# Tractive_System_Board_Rev3.net
KiCad netlist of a schematic drawn in EAGLE
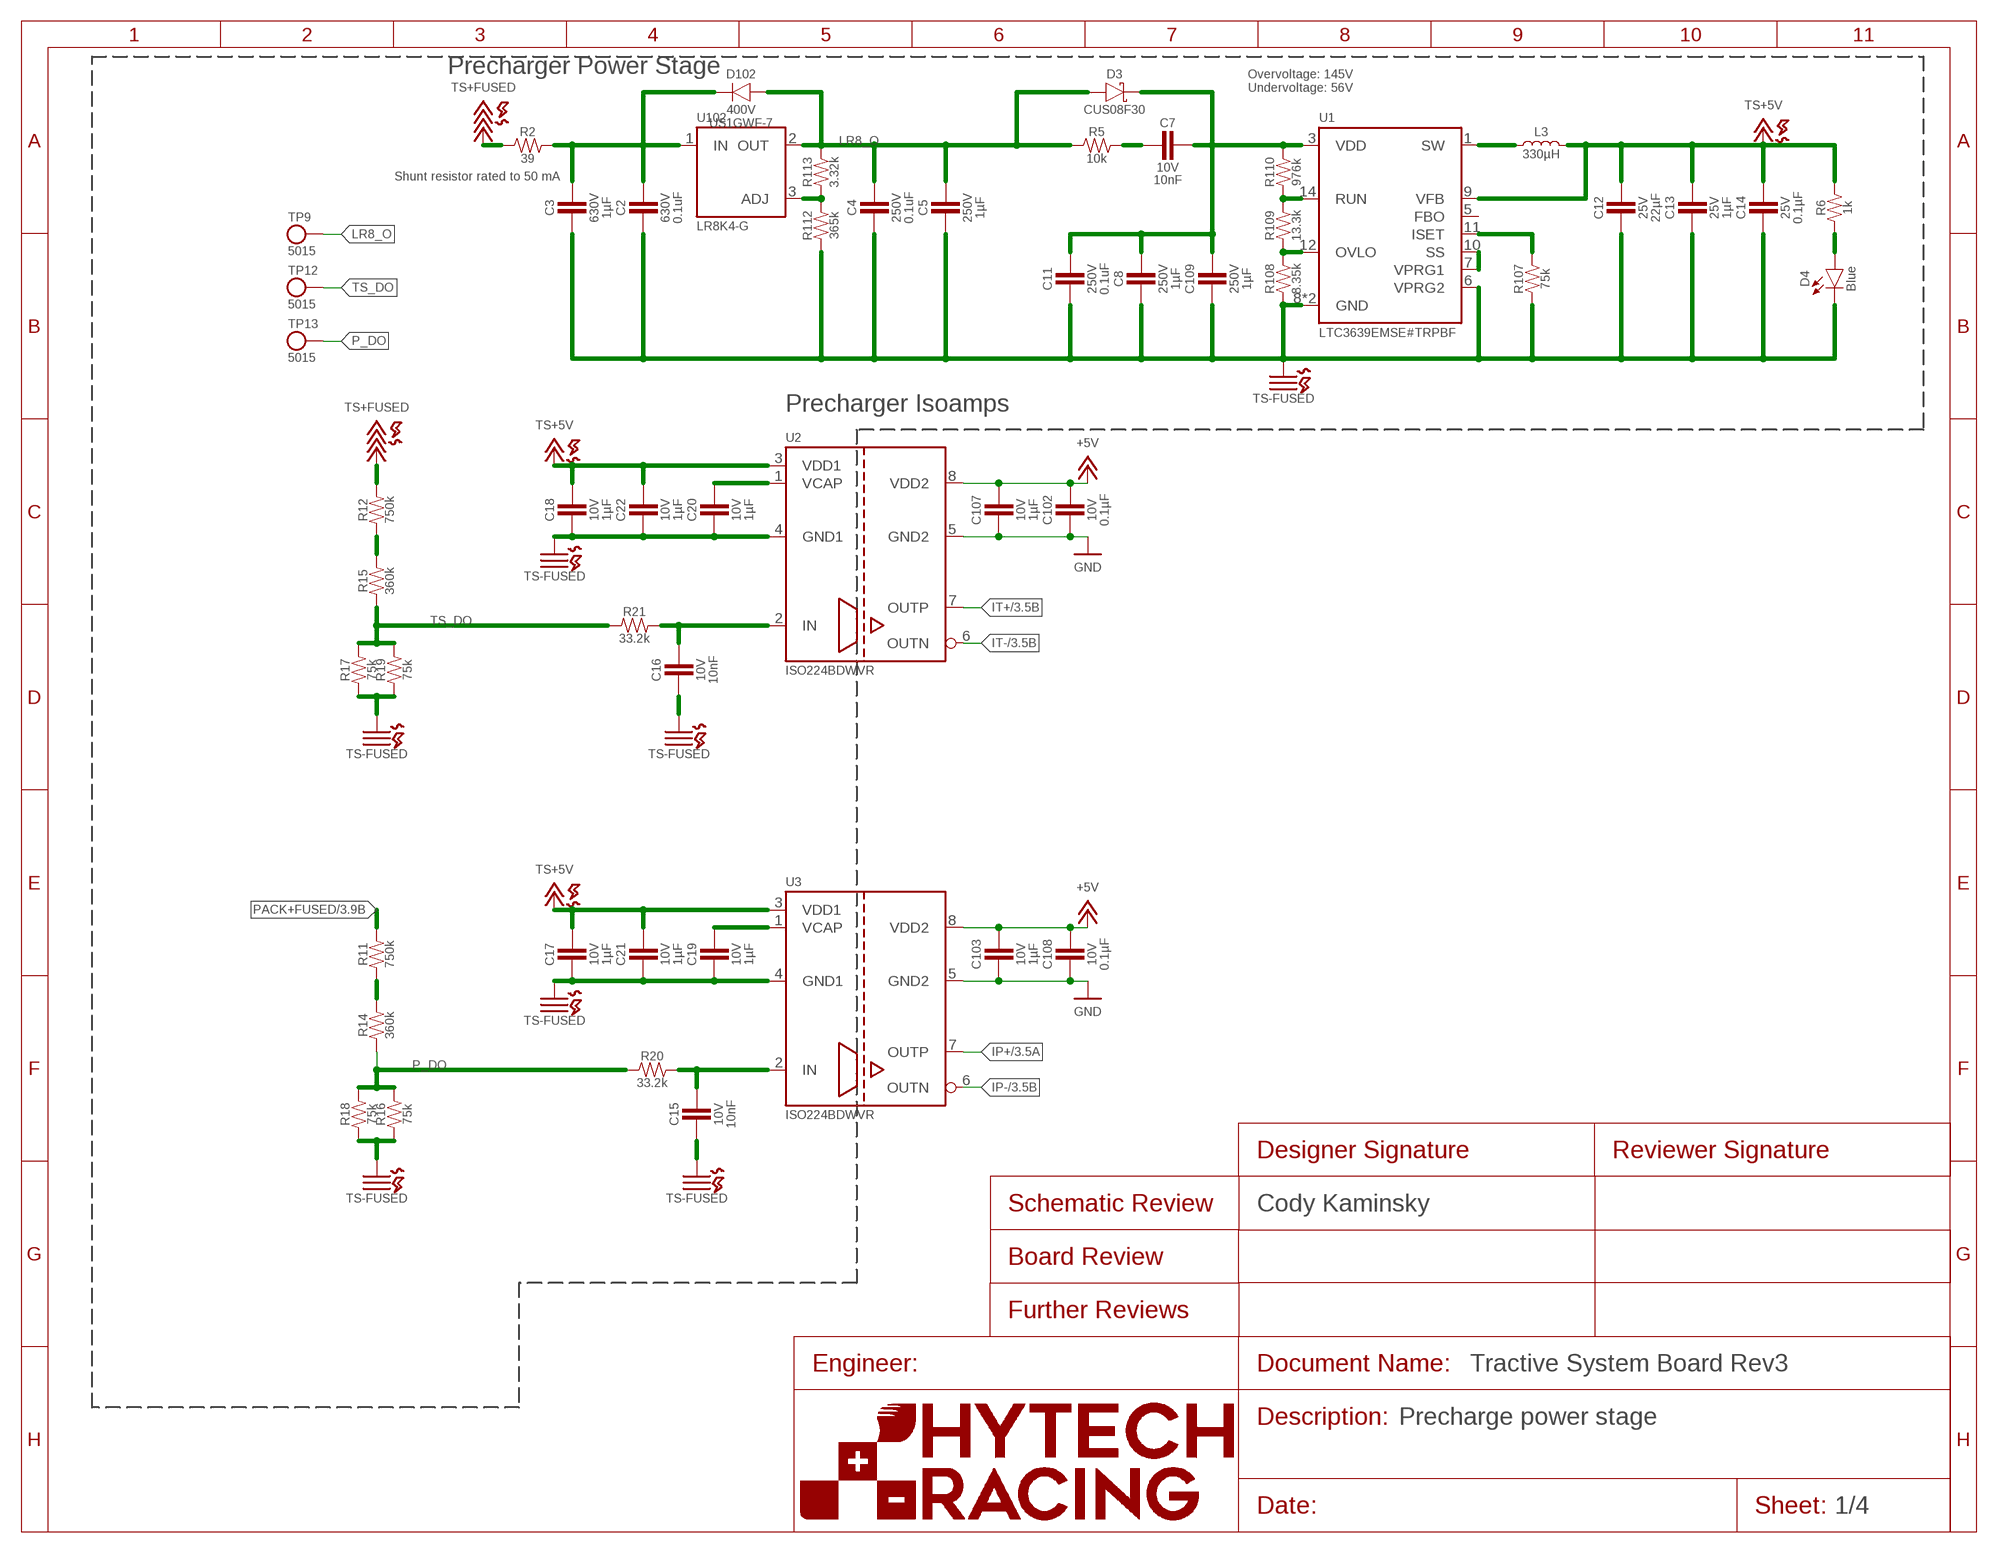
[diagram p0: schematic, sheet 1]
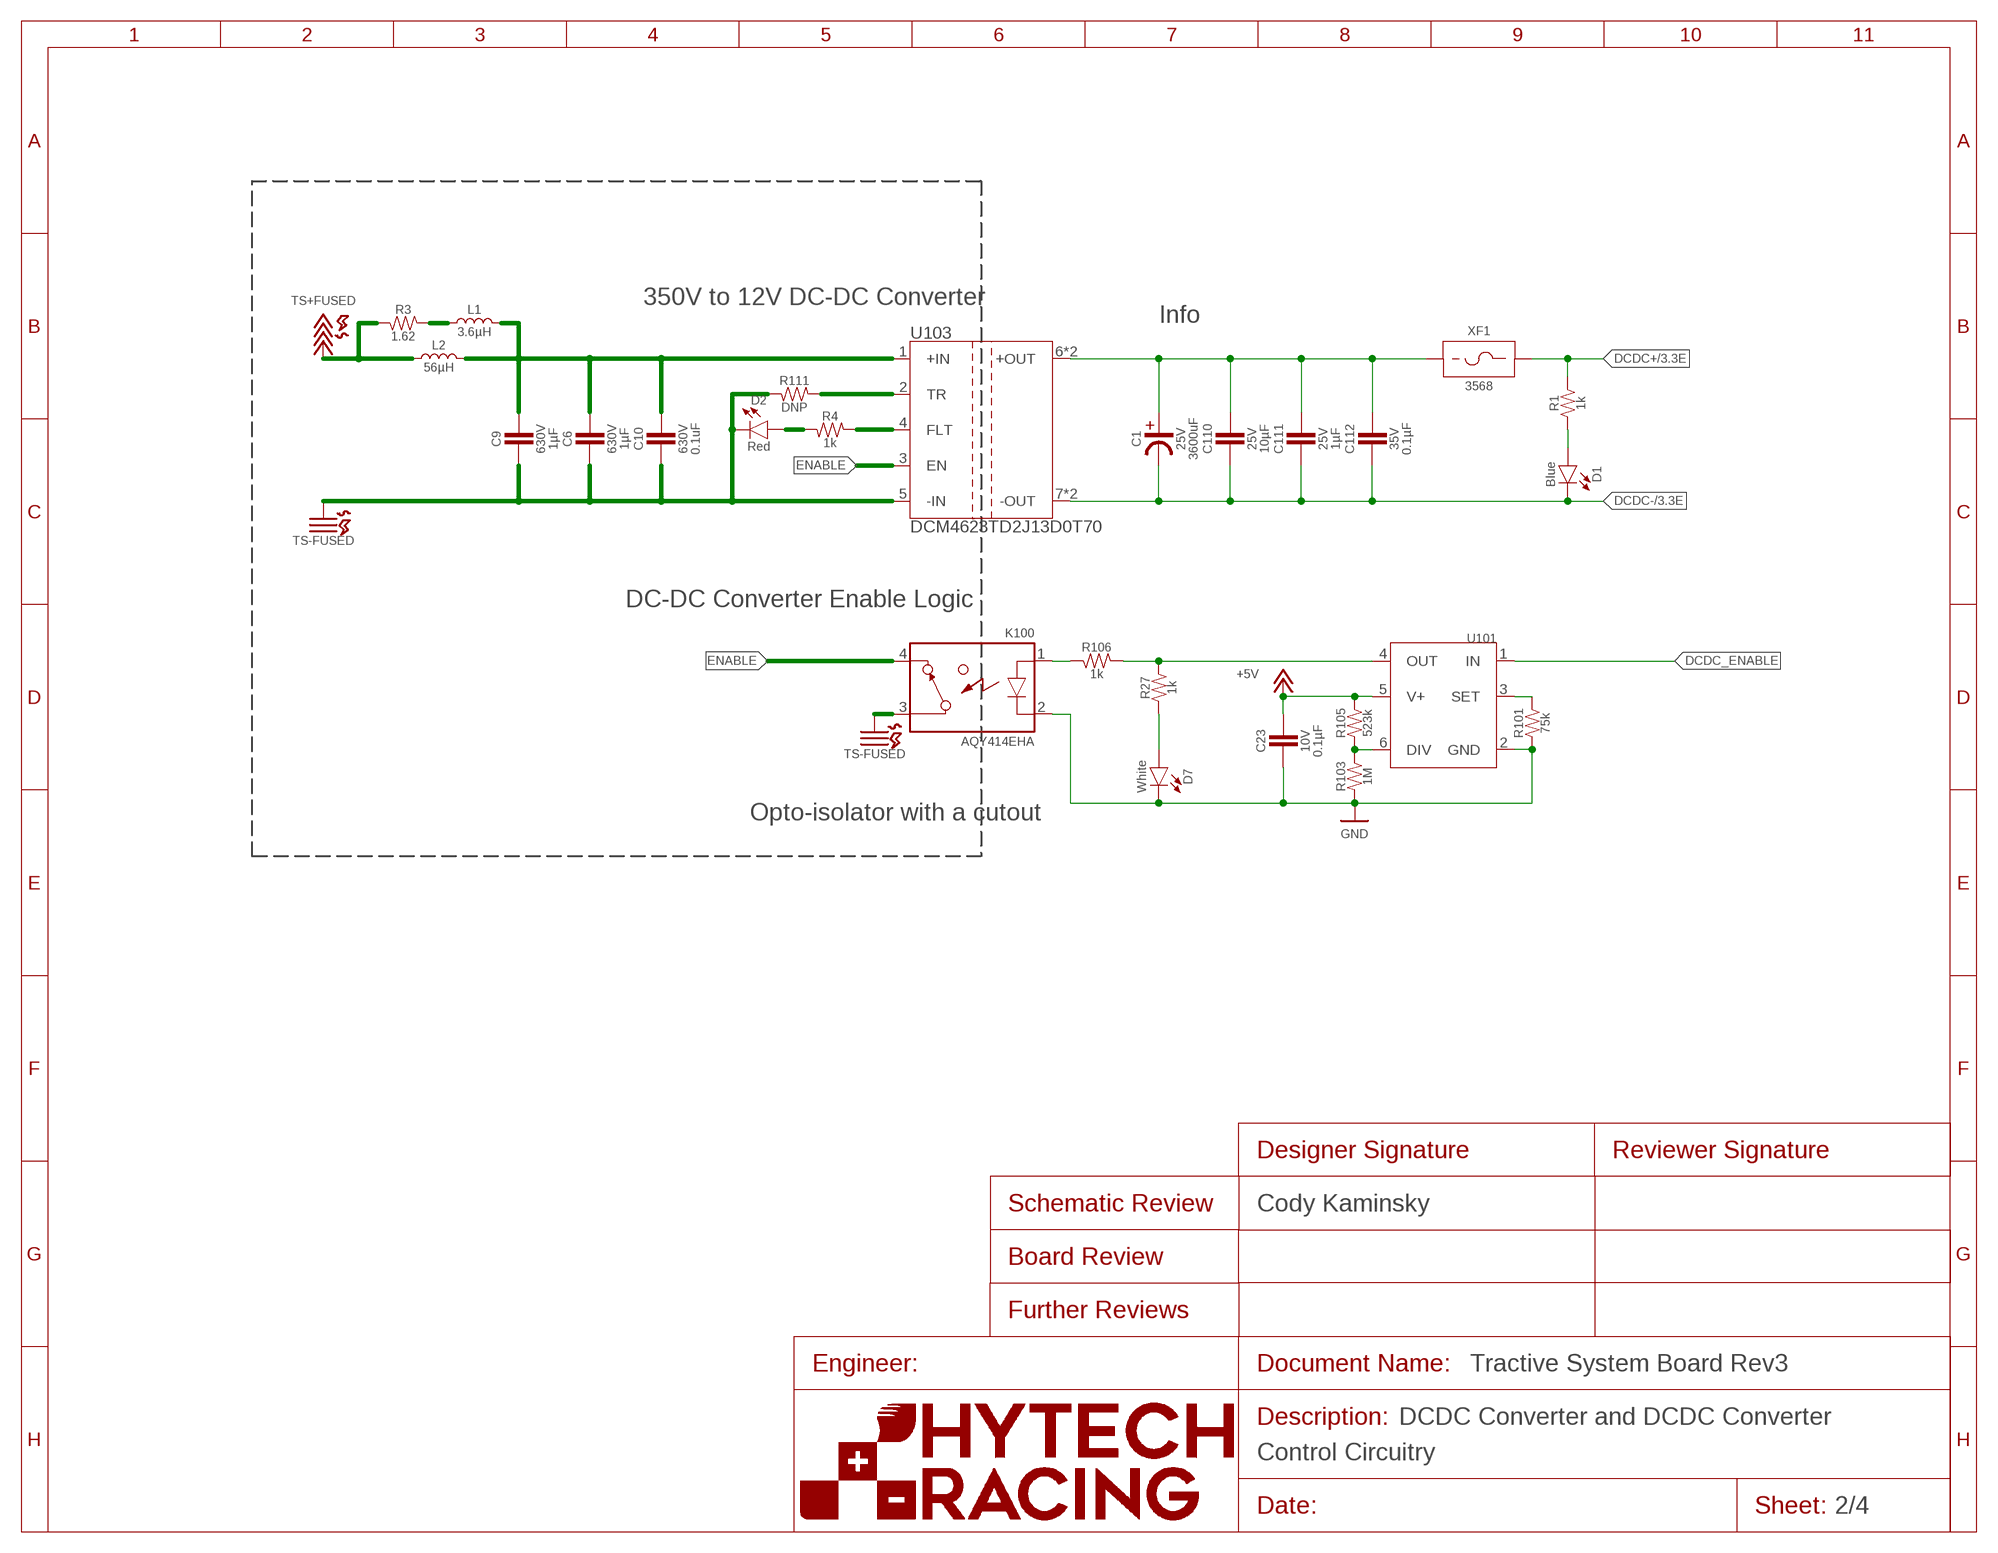
[diagram p1: schematic, sheet 2]
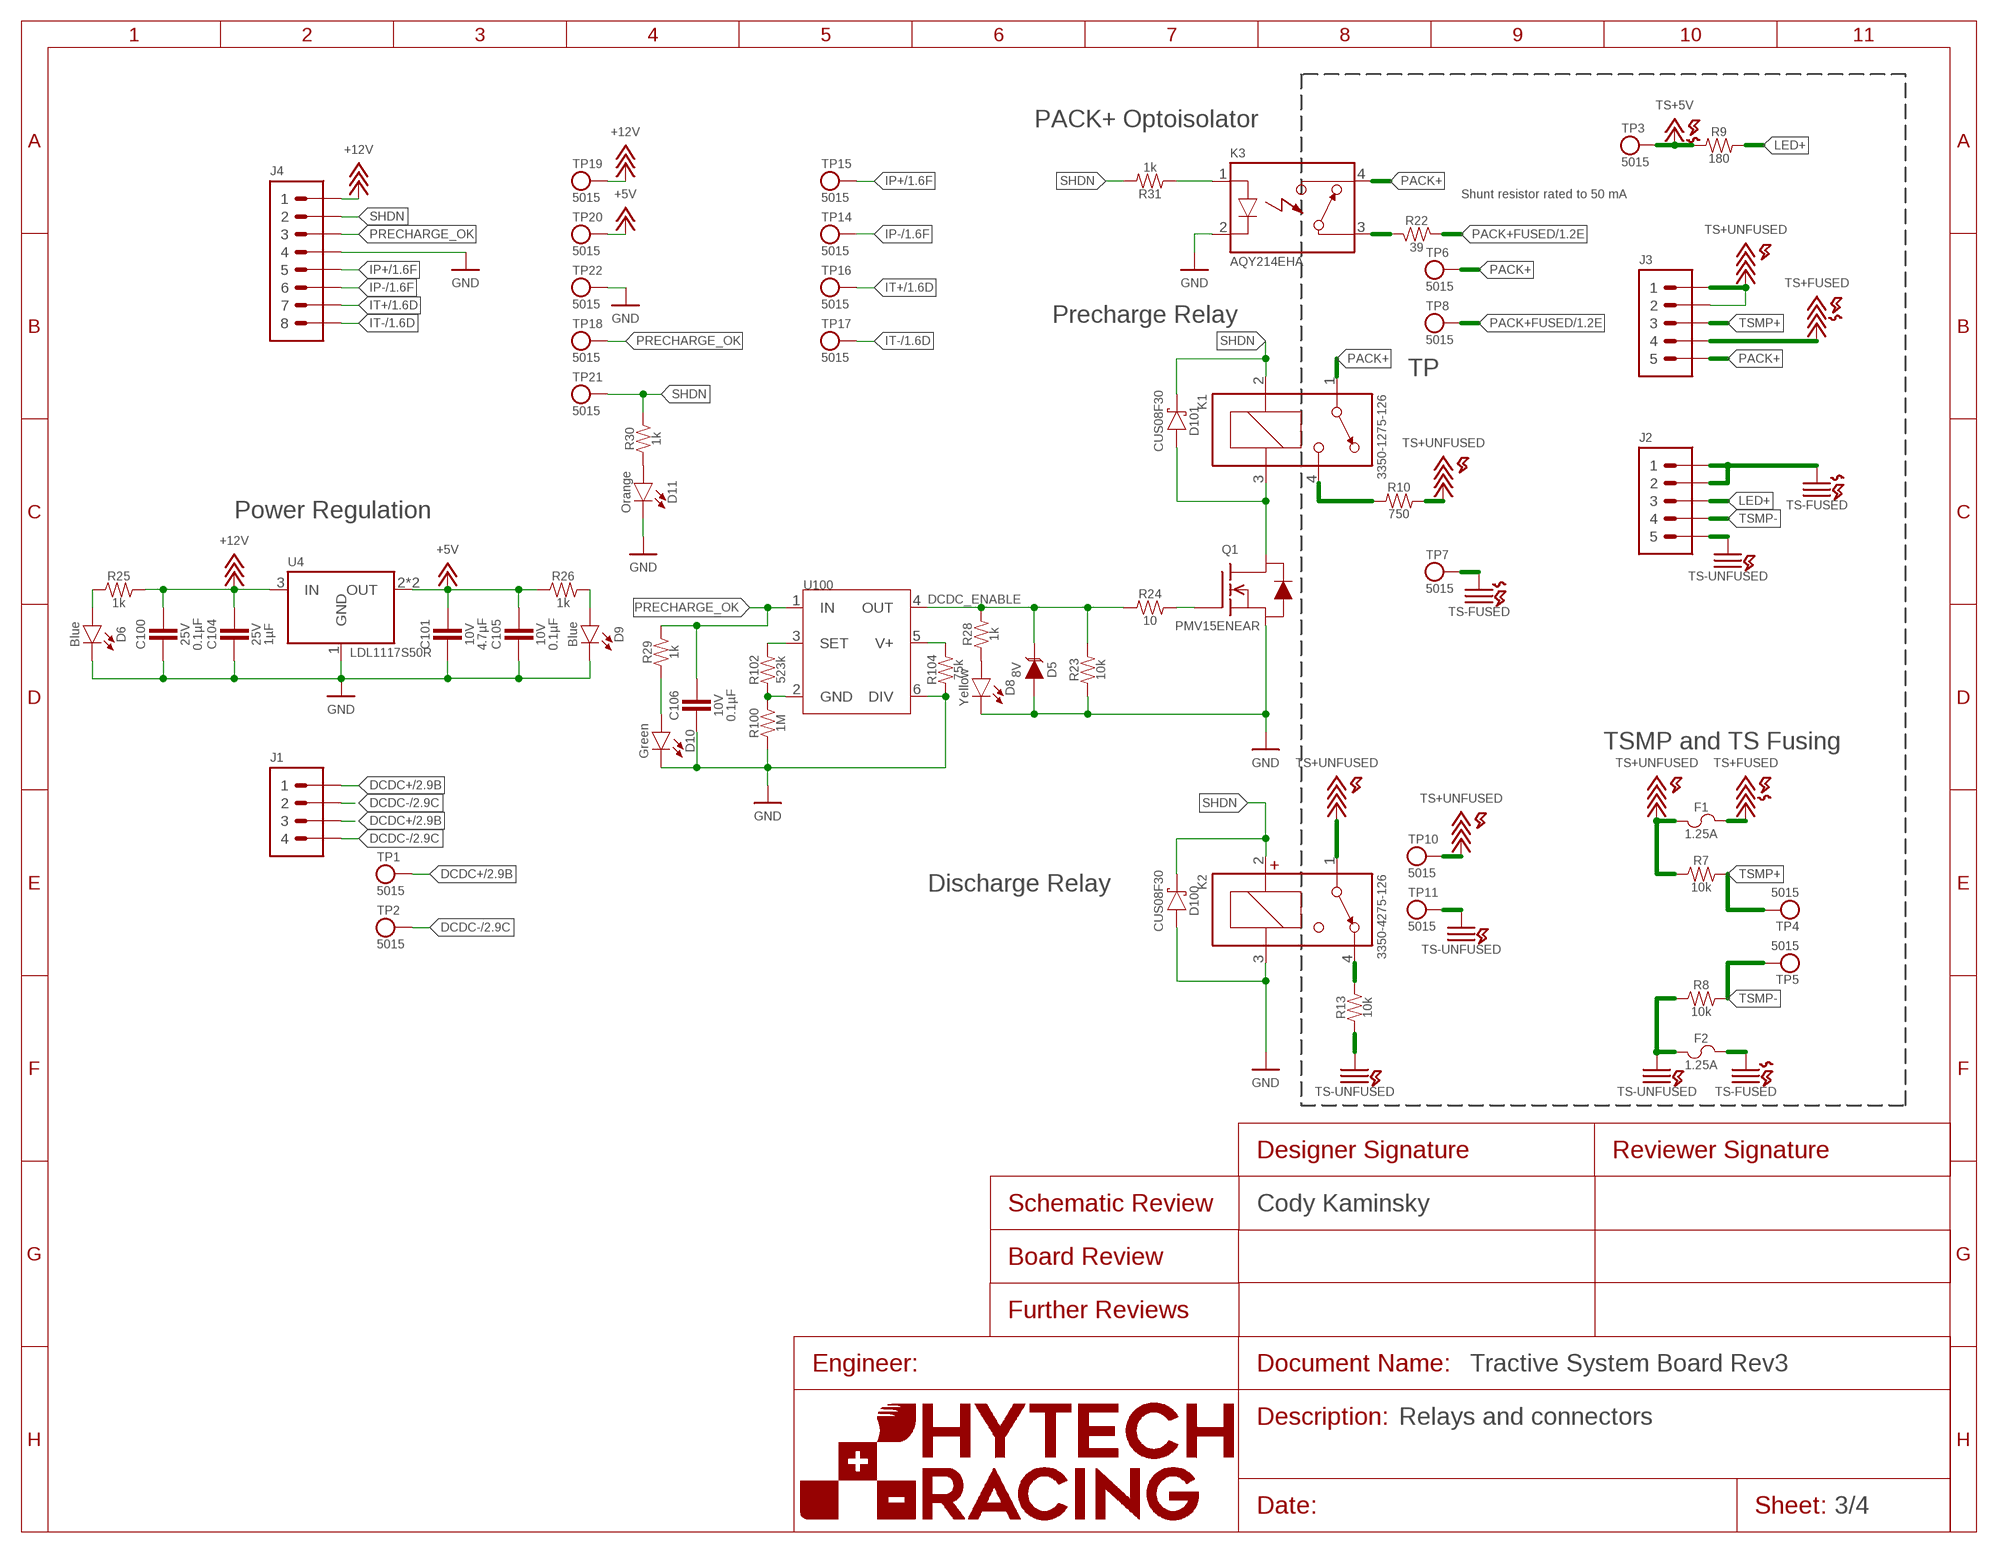
[diagram p2: schematic, sheet 3]
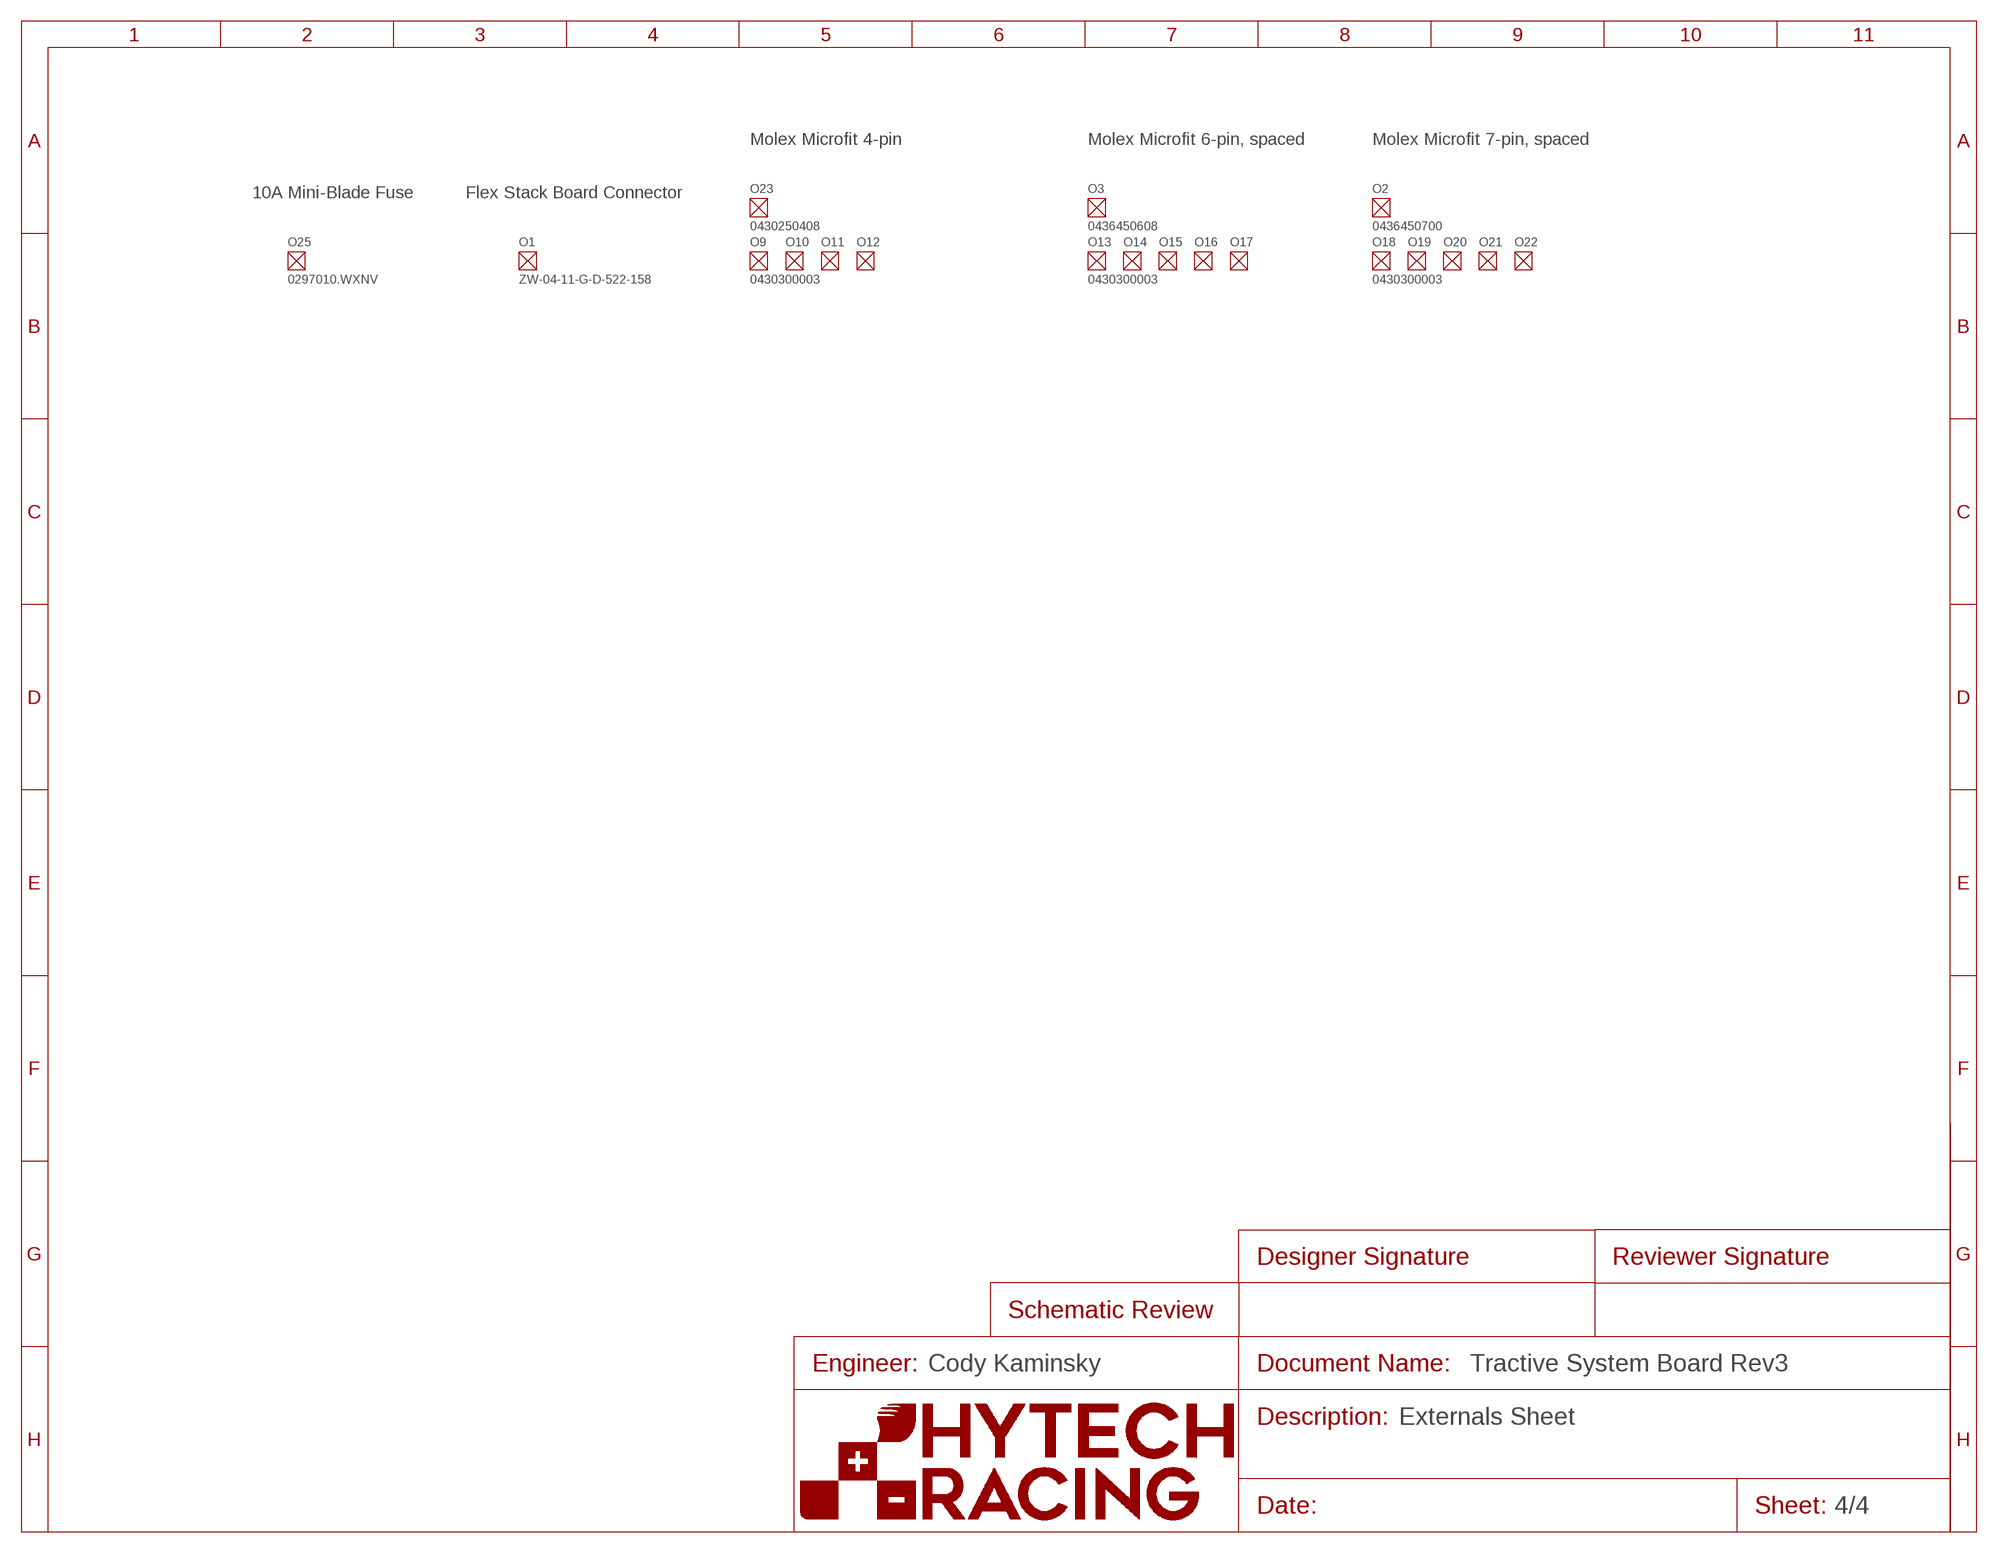
[diagram p3: schematic, sheet 4]

(export (version "E")
  (design (tool "Eeschema 10.0.6"))
  (components
    (comp (ref "C1")
      (value "CAPACITOR_POLAR__3600UF")
      (footprint "eagle-import:EKYC_MM")
      (fields
        (field (name "CAPACITANCE") "3600uF")
        (field (name "MANUFACTURER") "United Chemi-con")
        (field (name "MPN") "EKYC250ELL362ML20S")
        (field (name "VOLTAGE") "25V")
      )
      (libsource (lib "eagle-import") (part "CAPACITOR_POLAR_?_3600UF"))
    )
    (comp (ref "C6")
      (value "CAPACITOR_2220_630V_1UF")
      (footprint "eagle-import:2220-CAP")
      (fields
        (field (name "CAPACITANCE") "1µF")
        (field (name "MANUFACTURER") "Knowles Syfer")
        (field (name "MPN") "2220Y6300105KXTWS2")
        (field (name "TOLERANCE") "10%")
        (field (name "VOLTAGE") "630V")
      )
      (libsource (lib "eagle-import") (part "CAPACITOR_?_2220630V_1UF"))
    )
    (comp (ref "C9")
      (value "CAPACITOR_2220_630V_1UF")
      (footprint "eagle-import:2220-CAP")
      (fields
        (field (name "CAPACITANCE") "1µF")
        (field (name "MANUFACTURER") "Knowles Syfer")
        (field (name "MPN") "2220Y6300105KXTWS2")
        (field (name "TOLERANCE") "10%")
        (field (name "VOLTAGE") "630V")
      )
      (libsource (lib "eagle-import") (part "CAPACITOR_?_2220630V_1UF"))
    )
    (comp (ref "C10")
      (value "CAPACITOR_2220_630V_0.1UF")
      (footprint "eagle-import:2220-CAP")
      (fields
        (field (name "CAPACITANCE") "0.1uF")
        (field (name "MANUFACTURER") "TDK Coporation")
        (field (name "MPN") "C5750CH2J104K280KC")
        (field (name "TOLERANCE") "10%")
        (field (name "VOLTAGE") "630V")
      )
      (libsource (lib "eagle-import") (part "CAPACITOR_?_2220630V_0.1UF"))
    )
    (comp (ref "C23")
      (value "CAPACITOR_0603_10V_0.1UF")
      (footprint "eagle-import:0603-CAP")
      (fields
        (field (name "CAPACITANCE") "0.1µF")
        (field (name "MANUFACTURER") "Vishay Vitramon")
        (field (name "MPN") "VJ0603Y104JXQPW1BC")
        (field (name "TOLERANCE") "5%")
        (field (name "VOLTAGE") "10V")
      )
      (libsource (lib "eagle-import") (part "CAPACITOR_?_060310V_0.1UF"))
    )
    (comp (ref "C110")
      (value "CAPACITOR_0603_25V_10UF")
      (footprint "eagle-import:0603-CAP")
      (fields
        (field (name "CAPACITANCE") "10µF")
        (field (name "MANUFACTURER") "Murata Electronics")
        (field (name "MPN") "GRM188R61E106MA73D")
        (field (name "TOLERANCE") "20%")
        (field (name "VOLTAGE") "25V")
      )
      (libsource (lib "eagle-import") (part "CAPACITOR_?_060325V_10UF"))
    )
    (comp (ref "C111")
      (value "CAPACITOR_0603_25V_1UF")
      (footprint "eagle-import:0603-CAP")
      (fields
        (field (name "CAPACITANCE") "1µF")
        (field (name "MANUFACTURER") "Samsung Electro-Mechanics")
        (field (name "MPN") "CL10B105KA8NNNC")
        (field (name "TOLERANCE") "10%")
        (field (name "VOLTAGE") "25V")
      )
      (libsource (lib "eagle-import") (part "CAPACITOR_?_060325V_1UF"))
    )
    (comp (ref "C112")
      (value "CAPACITOR_0603_35V_0.1UF")
      (footprint "eagle-import:0603-CAP")
      (fields
        (field (name "CAPACITANCE") "0.1µF")
        (field (name "MANUFACTURER") "Taiyo Yuden")
        (field (name "MPN") "GMK107B7104KAHT")
        (field (name "TOLERANCE") "10%")
        (field (name "VOLTAGE") "35V")
      )
      (libsource (lib "eagle-import") (part "CAPACITOR_?_060335V_0.1UF"))
    )
    (comp (ref "D1")
      (value "LED_0603_BLUE")
      (footprint "eagle-import:0603-LED")
      (fields
        (field (name "COLOR") "Blue")
        (field (name "MANUFACTURER") "Kingbright")
        (field (name "MPN") "APT1608VBC/D")
      )
      (libsource (lib "eagle-import") (part "LED_?_0603BLUE"))
    )
    (comp (ref "D2")
      (value "LED_0603_RED")
      (footprint "eagle-import:0603-LED")
      (fields
        (field (name "COLOR") "Red")
        (field (name "MANUFACTURER") "Kingbright")
        (field (name "MPN") "APT1608SECK/J3-PRV")
      )
      (libsource (lib "eagle-import") (part "LED_?_0603RED"))
    )
    (comp (ref "D7")
      (value "LED_0603_WHITE")
      (footprint "eagle-import:0603-LED")
      (fields
        (field (name "COLOR") "White")
        (field (name "MANUFACTURER") "Bivar Inc.")
        (field (name "MPN") "SM0603UWC")
      )
      (libsource (lib "eagle-import") (part "LED_?_0603WHITE"))
    )
    (comp (ref "K100")
      (value "RELAY_SOLIDSTATE_NC_AG")
      (footprint "eagle-import:DIP-4_AIRGAP")
      (fields (field (name "MPN") "AQY414EHA") (field (name "MANUFACTURER") "Panasonic Industrial Devices"))
      (libsource (lib "eagle-import") (part "RELAY_SOLIDSTATE_NC_AG"))
    )
    (comp (ref "L1")
      (value "INDUCTOR_PA4334_3.6UH")
      (footprint "eagle-import:PA4334")
      (fields
        (field (name "INDUCTANCE") "3.6µH")
        (field (name "MANUFACTURER") "Pulse Electonics Company")
        (field (name "MPN") "PA4334.362NLT")
      )
      (libsource (lib "eagle-import") (part "INDUCTOR_?_PA43343.6UH"))
    )
    (comp (ref "L2")
      (value "INDUCTOR_WELMHI_56UH")
      (footprint "eagle-import:WE-LMHI")
      (fields
        (field (name "INDUCTANCE") "56µH")
        (field (name "MANUFACTURER") "Wurth Elektronik")
        (field (name "MPN") "74437349560")
        (field (name "TOLERANCE") "20%")
      )
      (libsource (lib "eagle-import") (part "INDUCTOR_?_WELMHI56UH"))
    )
    (comp (ref "R1")
      (value "RESISTOR_0603_1K")
      (footprint "eagle-import:0603-RES")
      (fields
        (field (name "MANUFACTURER") "Yageo")
        (field (name "MPN") "RC0603FR-071KL")
        (field (name "POWER") "0.1W")
        (field (name "RESISTANCE") "1k")
      )
      (libsource (lib "eagle-import") (part "RESISTOR_?_06031K"))
    )
    (comp (ref "R3")
      (value "RESISTOR_0603_1.62")
      (footprint "eagle-import:0603-RES")
      (fields
        (field (name "MANUFACTURER") "TE Conductivity Passive Product")
        (field (name "MPN") "CPF0603B1R62E1")
        (field (name "POWER") "0.1W")
        (field (name "RESISTANCE") "1.62")
      )
      (libsource (lib "eagle-import") (part "RESISTOR_?_06031.62"))
    )
    (comp (ref "R4")
      (value "RESISTOR_0603_1K")
      (footprint "eagle-import:0603-RES")
      (fields
        (field (name "MANUFACTURER") "Yageo")
        (field (name "MPN") "RC0603FR-071KL")
        (field (name "POWER") "0.1W")
        (field (name "RESISTANCE") "1k")
      )
      (libsource (lib "eagle-import") (part "RESISTOR_?_06031K"))
    )
    (comp (ref "R27")
      (value "RESISTOR_0603_1K")
      (footprint "eagle-import:0603-RES")
      (fields
        (field (name "MANUFACTURER") "Yageo")
        (field (name "MPN") "RC0603FR-071KL")
        (field (name "POWER") "0.1W")
        (field (name "RESISTANCE") "1k")
      )
      (libsource (lib "eagle-import") (part "RESISTOR_?_06031K"))
    )
    (comp (ref "R101")
      (value "RESISTOR_0603_75K")
      (footprint "eagle-import:0603-RES")
      (fields
        (field (name "MANUFACTURER") "Yageo")
        (field (name "MPN") "RT0603BRE0775KL")
        (field (name "POWER") "0.1W")
        (field (name "RESISTANCE") "75k")
      )
      (libsource (lib "eagle-import") (part "RESISTOR_?_060375K"))
    )
    (comp (ref "R103")
      (value "RESISTOR_0805_1M")
      (footprint "eagle-import:0805-RES")
      (fields
        (field (name "MANUFACTURER") "Panasonic Electronic Components")
        (field (name "MPN") "ERJ-PB6B1004V")
        (field (name "POWER") "0.25W")
        (field (name "RESISTANCE") "1M")
      )
      (libsource (lib "eagle-import") (part "RESISTOR_?_08051M"))
    )
    (comp (ref "R105")
      (value "RESISTOR_0805_523K")
      (footprint "eagle-import:0805-RES")
      (fields
        (field (name "MANUFACTURER") "Panasonic Electronic Components")
        (field (name "MPN") "ERJ-PB6B5233V")
        (field (name "POWER") "0.25W")
        (field (name "RESISTANCE") "523k")
      )
      (libsource (lib "eagle-import") (part "RESISTOR_?_0805523K"))
    )
    (comp (ref "R106")
      (value "RESISTOR_0603_1K")
      (footprint "eagle-import:0603-RES")
      (fields
        (field (name "MANUFACTURER") "Yageo")
        (field (name "MPN") "RC0603FR-071KL")
        (field (name "POWER") "0.1W")
        (field (name "RESISTANCE") "1k")
      )
      (libsource (lib "eagle-import") (part "RESISTOR_?_06031K"))
    )
    (comp (ref "R111")
      (value "RESISTOR_0603_DNP")
      (footprint "eagle-import:0603-RES")
      (fields (field (name "RESISTANCE") "DNP"))
      (libsource (lib "eagle-import") (part "RESISTOR_?_0603DNP"))
    )
    (comp (ref "U101")
      (value "LTC6994-2")
      (footprint "eagle-import:SOT-23-6")
      (libsource (lib "eagle-import") (part "LTC6994-2"))
    )
    (comp (ref "U103")
      (value "DCM4623TD2J13D0T70")
      (footprint "eagle-import:DCM4623")
      (fields (field (name "MANUFACTURER") "Vicor"))
      (libsource (lib "eagle-import") (part "DCM4623TD2J13D0T70"))
    )
    (comp (ref "XF1")
      (value "FUSE_HOLDER_MINIBLADEPTH")
      (footprint "eagle-import:3568")
      (fields (field (name "MANUFACTURER") "Keystone") (field (name "MPN") "3568"))
      (libsource (lib "eagle-import") (part "FUSE_HOLDER_PTHMINIBLADE"))
    )
    (comp (ref "C100")
      (value "CAPACITOR_0603_25V_0.1UF")
      (footprint "eagle-import:0603-CAP")
      (fields
        (field (name "CAPACITANCE") "0.1µF")
        (field (name "MANUFACTURER") "Samsung Electro-Mechanics")
        (field (name "MPN") "CL10B104KA8NNNC")
        (field (name "TOLERANCE") "10%")
        (field (name "VOLTAGE") "25V")
      )
      (libsource (lib "eagle-import") (part "CAPACITOR_?_060325V_0.1UF"))
    )
    (comp (ref "C101")
      (value "CAPACITOR_0603_10V_4.7UF")
      (footprint "eagle-import:0603-CAP")
      (fields
        (field (name "CAPACITANCE") "4.7µF")
        (field (name "MANUFACTURER") "Samsung Electro-Mechanics")
        (field (name "MPN") "CL10A475KP8NNNC")
        (field (name "TOLERANCE") "10%")
        (field (name "VOLTAGE") "10V")
      )
      (libsource (lib "eagle-import") (part "CAPACITOR_?_060310V_4.7UF"))
    )
    (comp (ref "C104")
      (value "CAPACITOR_0603_25V_1UF")
      (footprint "eagle-import:0603-CAP")
      (fields
        (field (name "CAPACITANCE") "1µF")
        (field (name "MANUFACTURER") "Samsung Electro-Mechanics")
        (field (name "MPN") "CL10B105KA8NNNC")
        (field (name "TOLERANCE") "10%")
        (field (name "VOLTAGE") "25V")
      )
      (libsource (lib "eagle-import") (part "CAPACITOR_?_060325V_1UF"))
    )
    (comp (ref "C105")
      (value "CAPACITOR_0603_10V_0.1UF")
      (footprint "eagle-import:0603-CAP")
      (fields
        (field (name "CAPACITANCE") "0.1µF")
        (field (name "MANUFACTURER") "Vishay Vitramon")
        (field (name "MPN") "VJ0603Y104JXQPW1BC")
        (field (name "TOLERANCE") "5%")
        (field (name "VOLTAGE") "10V")
      )
      (libsource (lib "eagle-import") (part "CAPACITOR_?_060310V_0.1UF"))
    )
    (comp (ref "C106")
      (value "CAPACITOR_0603_10V_0.1UF")
      (footprint "eagle-import:0603-CAP")
      (fields
        (field (name "CAPACITANCE") "0.1µF")
        (field (name "MANUFACTURER") "Vishay Vitramon")
        (field (name "MPN") "VJ0603Y104JXQPW1BC")
        (field (name "TOLERANCE") "5%")
        (field (name "VOLTAGE") "10V")
      )
      (libsource (lib "eagle-import") (part "CAPACITOR_?_060310V_0.1UF"))
    )
    (comp (ref "D5")
      (value "TVS_8V")
      (footprint "eagle-import:SOT-23")
      (fields
        (field (name "MANUFACTURER") "Vishay General Semiconductor - Diodes Division")
        (field (name "MPN") "GSOT08-E3-08")
        (field (name "VOLTAGE") "8V")
      )
      (libsource (lib "eagle-import") (part "TVS_8V"))
    )
    (comp (ref "D6")
      (value "LED_0603_BLUE")
      (footprint "eagle-import:0603-LED")
      (fields
        (field (name "COLOR") "Blue")
        (field (name "MANUFACTURER") "Kingbright")
        (field (name "MPN") "APT1608VBC/D")
      )
      (libsource (lib "eagle-import") (part "LED_?_0603BLUE"))
    )
    (comp (ref "D8")
      (value "LED_0603_YELLOW")
      (footprint "eagle-import:0603-LED")
      (fields
        (field (name "COLOR") "Yellow")
        (field (name "MANUFACTURER") "Kingbright")
        (field (name "MPN") "APT1608SYCK/J3-PRV")
      )
      (libsource (lib "eagle-import") (part "LED_?_0603YELLOW"))
    )
    (comp (ref "D9")
      (value "LED_0603_BLUE")
      (footprint "eagle-import:0603-LED")
      (fields
        (field (name "COLOR") "Blue")
        (field (name "MANUFACTURER") "Kingbright")
        (field (name "MPN") "APT1608VBC/D")
      )
      (libsource (lib "eagle-import") (part "LED_?_0603BLUE"))
    )
    (comp (ref "D10")
      (value "LED_0603_GREEN")
      (footprint "eagle-import:0603-LED")
      (fields
        (field (name "COLOR") "Green")
        (field (name "MANUFACTURER") "Kingbright")
        (field (name "MPN") "APT1608ZGCK")
      )
      (libsource (lib "eagle-import") (part "LED_?_0603GREEN"))
    )
    (comp (ref "D11")
      (value "LED_0603_ORANGE")
      (footprint "eagle-import:0603-LED")
      (fields
        (field (name "COLOR") "Orange")
        (field (name "MANUFACTURER") "Kingbright")
        (field (name "MPN") "APT1608SECK")
      )
      (libsource (lib "eagle-import") (part "LED_?_0603ORANGE"))
    )
    (comp (ref "D100")
      (value "SCHOTTKY_SOD323_30V")
      (footprint "eagle-import:SOD-323")
      (fields
        (field (name "MANUFACTURER") "Toshiba Semiconductor and Storage")
        (field (name "MPN") "CUS08F30")
        (field (name "VOLTAGE") "30V")
      )
      (libsource (lib "eagle-import") (part "SCHOTTKY_?_SOD32330V"))
    )
    (comp (ref "D101")
      (value "SCHOTTKY_SOD323_30V")
      (footprint "eagle-import:SOD-323")
      (fields
        (field (name "MANUFACTURER") "Toshiba Semiconductor and Storage")
        (field (name "MPN") "CUS08F30")
        (field (name "VOLTAGE") "30V")
      )
      (libsource (lib "eagle-import") (part "SCHOTTKY_?_SOD32330V"))
    )
    (comp (ref "F1")
      (value "FUSE_0885_1.25")
      (footprint "eagle-import:0885")
      (fields
        (field (name "CURRENT") "1.25A")
        (field (name "MANUFACTURER") "Littelfuse Inc.")
        (field (name "MPN") "08851.25DR")
        (field (name "VOLTAGE") "500V")
      )
      (libsource (lib "eagle-import") (part "FUSE_?_08851.25"))
    )
    (comp (ref "F2")
      (value "FUSE_0885_1.25")
      (footprint "eagle-import:0885")
      (fields
        (field (name "CURRENT") "1.25A")
        (field (name "MANUFACTURER") "Littelfuse Inc.")
        (field (name "MPN") "08851.25DR")
        (field (name "VOLTAGE") "500V")
      )
      (libsource (lib "eagle-import") (part "FUSE_?_08851.25"))
    )
    (comp (ref "J1")
      (value "CONNECTOR-4__")
      (footprint "eagle-import:MOLEX_MICROFIT_PTH_VERTICAL_04_DUAL")
      (fields (field (name "MPN") "2068320423") (field (name "MANUFACTURER") "Molex"))
      (libsource (lib "eagle-import") (part "CONNECTOR-4_?_"))
    )
    (comp (ref "J2")
      (value "CONNECTOR-5_MICRO_V6S_")
      (footprint "eagle-import:MOLEX_MICROFIT_PTH_VERTICAL_06_SINGLE_SPACED")
      (fields (field (name "MPN") "2165713006") (field (name "MANUFACTURER") "Molex"))
      (libsource (lib "eagle-import") (part "CONNECTOR-5_?_MICRO_V6S"))
    )
    (comp (ref "J3")
      (value "CONNECTOR-5_MICRO_V7S_")
      (footprint "eagle-import:MOLEX_MICROFIT_PTH_VERTICAL_07_SINGLE_SPACED")
      (fields (field (name "MPN") "2165713007") (field (name "MANUFACTURER") "Molex"))
      (libsource (lib "eagle-import") (part "CONNECTOR-5_?_MICRO_V7S"))
    )
    (comp (ref "J4")
      (value "CONNECTOR-8_S_S")
      (footprint "eagle-import:FLEX_STACK_PTH_08_DUAL")
      (fields
        (field (name "MANUFACTURER") "Sullins Connector Solutions")
        (field (name "MPN") "PPPC042LFBN-RC")
      )
      (libsource (lib "eagle-import") (part "CONNECTOR-8_?_SS"))
    )
    (comp (ref "K1")
      (value "RELAY_SPST_NO_3550_12")
      (footprint "eagle-import:335X")
      (fields (field (name "MANUFACTURER") "Comus International") (field (name "MPN") "3350-1275-126"))
      (libsource (lib "eagle-import") (part "RELAY_SPST_NO_?3550_12"))
    )
    (comp (ref "K2")
      (value "RELAY_SPST_NC_POLARIZED_3550_12")
      (footprint "eagle-import:335X")
      (fields (field (name "MANUFACTURER") "Comus International") (field (name "MPN") "3350-4275-126"))
      (libsource (lib "eagle-import") (part "RELAY_SPST_NC_POLARIZED_?3550_12"))
    )
    (comp (ref "K3")
      (value "RELAY_SOLIDSTATE_NO_AG")
      (footprint "eagle-import:DIP-4_AIRGAP")
      (fields (field (name "MPN") "AQY214EHA") (field (name "MANUFACTURER") "Panasonic Inustrial Devices"))
      (libsource (lib "eagle-import") (part "RELAY_SOLIDSTATE_NO_AG"))
    )
    (comp (ref "Q1")
      (value "TRANSISTOR_N_MOS__PMV15ENEA")
      (footprint "eagle-import:SOT-23")
      (fields (field (name "MANUFACTURER") "Nexperia USA Inc.") (field (name "MPN") "PMV15ENEAR"))
      (libsource (lib "eagle-import") (part "TRANSISTOR_N_MOS_?_PMV15ENEA"))
    )
    (comp (ref "R7")
      (value "RESISTOR_B20_10K")
      (footprint "eagle-import:B20")
      (fields
        (field (name "MANUFACTURER") "Ohmite")
        (field (name "MPN") "B20J10KE")
        (field (name "POWER") "20W")
        (field (name "RESISTANCE") "10k")
      )
      (libsource (lib "eagle-import") (part "RESISTOR_?_B2010K"))
    )
    (comp (ref "R8")
      (value "RESISTOR_B20_10K")
      (footprint "eagle-import:B20")
      (fields
        (field (name "MANUFACTURER") "Ohmite")
        (field (name "MPN") "B20J10KE")
        (field (name "POWER") "20W")
        (field (name "RESISTANCE") "10k")
      )
      (libsource (lib "eagle-import") (part "RESISTOR_?_B2010K"))
    )
    (comp (ref "R9")
      (value "RESISTOR_0603_180")
      (footprint "eagle-import:0603-RES")
      (fields
        (field (name "MANUFACTURER") "Yageo")
        (field (name "MPN") "RC0603FR-07180RL")
        (field (name "POWER") "0.1W")
        (field (name "RESISTANCE") "180")
      )
      (libsource (lib "eagle-import") (part "RESISTOR_?_0603180"))
    )
    (comp (ref "R10")
      (value "RESISTOR_B20_750")
      (footprint "eagle-import:B20")
      (fields
        (field (name "MANUFACTURER") "Ohmite")
        (field (name "MPN") "B20J750E")
        (field (name "POWER") "20W")
        (field (name "RESISTANCE") "750")
      )
      (libsource (lib "eagle-import") (part "RESISTOR_?_B20750"))
    )
    (comp (ref "R13")
      (value "RESISTOR_B20_10K")
      (footprint "eagle-import:B20")
      (fields
        (field (name "MANUFACTURER") "Ohmite")
        (field (name "MPN") "B20J10KE")
        (field (name "POWER") "20W")
        (field (name "RESISTANCE") "10k")
      )
      (libsource (lib "eagle-import") (part "RESISTOR_?_B2010K"))
    )
    (comp (ref "R22")
      (value "RESISTOR_0603_39")
      (footprint "eagle-import:0603-RES")
      (fields
        (field (name "MANUFACTURER") "Yageo")
        (field (name "MPN") "RT0603BRD0739RL")
        (field (name "POWER") "0.1W")
        (field (name "RESISTANCE") "39")
      )
      (libsource (lib "eagle-import") (part "RESISTOR_?_060339"))
    )
    (comp (ref "R23")
      (value "RESISTOR_0603_10K")
      (footprint "eagle-import:0603-RES")
      (fields
        (field (name "MANUFACTURER") "Yageo")
        (field (name "MPN") "RC0603FR-0710KL")
        (field (name "POWER") "0.1W")
        (field (name "RESISTANCE") "10k")
      )
      (libsource (lib "eagle-import") (part "RESISTOR_?_060310K"))
    )
    (comp (ref "R24")
      (value "RESISTOR_0603_10")
      (footprint "eagle-import:0603-RES")
      (fields
        (field (name "MANUFACTURER") "Yageo")
        (field (name "MPN") "RC0603FR-0710RL")
        (field (name "POWER") "0.1W")
        (field (name "RESISTANCE") "10")
      )
      (libsource (lib "eagle-import") (part "RESISTOR_?_060310"))
    )
    (comp (ref "R25")
      (value "RESISTOR_0603_1K")
      (footprint "eagle-import:0603-RES")
      (fields
        (field (name "MANUFACTURER") "Yageo")
        (field (name "MPN") "RC0603FR-071KL")
        (field (name "POWER") "0.1W")
        (field (name "RESISTANCE") "1k")
      )
      (libsource (lib "eagle-import") (part "RESISTOR_?_06031K"))
    )
    (comp (ref "R26")
      (value "RESISTOR_0603_1K")
      (footprint "eagle-import:0603-RES")
      (fields
        (field (name "MANUFACTURER") "Yageo")
        (field (name "MPN") "RC0603FR-071KL")
        (field (name "POWER") "0.1W")
        (field (name "RESISTANCE") "1k")
      )
      (libsource (lib "eagle-import") (part "RESISTOR_?_06031K"))
    )
    (comp (ref "R28")
      (value "RESISTOR_0603_1K")
      (footprint "eagle-import:0603-RES")
      (fields
        (field (name "MANUFACTURER") "Yageo")
        (field (name "MPN") "RC0603FR-071KL")
        (field (name "POWER") "0.1W")
        (field (name "RESISTANCE") "1k")
      )
      (libsource (lib "eagle-import") (part "RESISTOR_?_06031K"))
    )
    (comp (ref "R29")
      (value "RESISTOR_0603_1K")
      (footprint "eagle-import:0603-RES")
      (fields
        (field (name "MANUFACTURER") "Yageo")
        (field (name "MPN") "RC0603FR-071KL")
        (field (name "POWER") "0.1W")
        (field (name "RESISTANCE") "1k")
      )
      (libsource (lib "eagle-import") (part "RESISTOR_?_06031K"))
    )
    (comp (ref "R30")
      (value "RESISTOR_0603_1K")
      (footprint "eagle-import:0603-RES")
      (fields
        (field (name "MANUFACTURER") "Yageo")
        (field (name "MPN") "RC0603FR-071KL")
        (field (name "POWER") "0.1W")
        (field (name "RESISTANCE") "1k")
      )
      (libsource (lib "eagle-import") (part "RESISTOR_?_06031K"))
    )
    (comp (ref "R31")
      (value "RESISTOR_0603_1K")
      (footprint "eagle-import:0603-RES")
      (fields
        (field (name "MANUFACTURER") "Yageo")
        (field (name "MPN") "RC0603FR-071KL")
        (field (name "POWER") "0.1W")
        (field (name "RESISTANCE") "1k")
      )
      (libsource (lib "eagle-import") (part "RESISTOR_?_06031K"))
    )
    (comp (ref "R100")
      (value "RESISTOR_0805_1M")
      (footprint "eagle-import:0805-RES")
      (fields
        (field (name "MANUFACTURER") "Panasonic Electronic Components")
        (field (name "MPN") "ERJ-PB6B1004V")
        (field (name "POWER") "0.25W")
        (field (name "RESISTANCE") "1M")
      )
      (libsource (lib "eagle-import") (part "RESISTOR_?_08051M"))
    )
    (comp (ref "R102")
      (value "RESISTOR_0805_523K")
      (footprint "eagle-import:0805-RES")
      (fields
        (field (name "MANUFACTURER") "Panasonic Electronic Components")
        (field (name "MPN") "ERJ-PB6B5233V")
        (field (name "POWER") "0.25W")
        (field (name "RESISTANCE") "523k")
      )
      (libsource (lib "eagle-import") (part "RESISTOR_?_0805523K"))
    )
    (comp (ref "R104")
      (value "RESISTOR_0603_75K")
      (footprint "eagle-import:0603-RES")
      (fields
        (field (name "MANUFACTURER") "Yageo")
        (field (name "MPN") "RT0603BRE0775KL")
        (field (name "POWER") "0.1W")
        (field (name "RESISTANCE") "75k")
      )
      (libsource (lib "eagle-import") (part "RESISTOR_?_060375K"))
    )
    (comp (ref "TP1")
      (value "TEST_POINT")
      (footprint "eagle-import:MICRO_MINIATURE")
      (fields (field (name "MPN") "5015") (field (name "MANUFACTURER") "Keystone Electronics"))
      (libsource (lib "eagle-import") (part "TEST_POINT"))
    )
    (comp (ref "TP2")
      (value "TEST_POINT")
      (footprint "eagle-import:MICRO_MINIATURE")
      (fields (field (name "MPN") "5015") (field (name "MANUFACTURER") "Keystone Electronics"))
      (libsource (lib "eagle-import") (part "TEST_POINT"))
    )
    (comp (ref "TP3")
      (value "TEST_POINT")
      (footprint "eagle-import:MICRO_MINIATURE")
      (fields (field (name "MPN") "5015") (field (name "MANUFACTURER") "Keystone Electronics"))
      (libsource (lib "eagle-import") (part "TEST_POINT"))
    )
    (comp (ref "TP4")
      (value "TEST_POINT")
      (footprint "eagle-import:MICRO_MINIATURE")
      (fields (field (name "MPN") "5015") (field (name "MANUFACTURER") "Keystone Electronics"))
      (libsource (lib "eagle-import") (part "TEST_POINT"))
    )
    (comp (ref "TP5")
      (value "TEST_POINT")
      (footprint "eagle-import:MICRO_MINIATURE")
      (fields (field (name "MPN") "5015") (field (name "MANUFACTURER") "Keystone Electronics"))
      (libsource (lib "eagle-import") (part "TEST_POINT"))
    )
    (comp (ref "TP6")
      (value "TEST_POINT")
      (footprint "eagle-import:MICRO_MINIATURE")
      (fields (field (name "MPN") "5015") (field (name "MANUFACTURER") "Keystone Electronics"))
      (libsource (lib "eagle-import") (part "TEST_POINT"))
    )
    (comp (ref "TP7")
      (value "TEST_POINT")
      (footprint "eagle-import:MICRO_MINIATURE")
      (fields (field (name "MPN") "5015") (field (name "MANUFACTURER") "Keystone Electronics"))
      (libsource (lib "eagle-import") (part "TEST_POINT"))
    )
    (comp (ref "TP8")
      (value "TEST_POINT")
      (footprint "eagle-import:MICRO_MINIATURE")
      (fields (field (name "MPN") "5015") (field (name "MANUFACTURER") "Keystone Electronics"))
      (libsource (lib "eagle-import") (part "TEST_POINT"))
    )
    (comp (ref "TP10")
      (value "TEST_POINT")
      (footprint "eagle-import:MICRO_MINIATURE")
      (fields (field (name "MPN") "5015") (field (name "MANUFACTURER") "Keystone Electronics"))
      (libsource (lib "eagle-import") (part "TEST_POINT"))
    )
    (comp (ref "TP11")
      (value "TEST_POINT")
      (footprint "eagle-import:MICRO_MINIATURE")
      (fields (field (name "MPN") "5015") (field (name "MANUFACTURER") "Keystone Electronics"))
      (libsource (lib "eagle-import") (part "TEST_POINT"))
    )
    (comp (ref "TP14")
      (value "TEST_POINT")
      (footprint "eagle-import:MICRO_MINIATURE")
      (fields (field (name "MPN") "5015") (field (name "MANUFACTURER") "Keystone Electronics"))
      (libsource (lib "eagle-import") (part "TEST_POINT"))
    )
    (comp (ref "TP15")
      (value "TEST_POINT")
      (footprint "eagle-import:MICRO_MINIATURE")
      (fields (field (name "MPN") "5015") (field (name "MANUFACTURER") "Keystone Electronics"))
      (libsource (lib "eagle-import") (part "TEST_POINT"))
    )
    (comp (ref "TP16")
      (value "TEST_POINT")
      (footprint "eagle-import:MICRO_MINIATURE")
      (fields (field (name "MPN") "5015") (field (name "MANUFACTURER") "Keystone Electronics"))
      (libsource (lib "eagle-import") (part "TEST_POINT"))
    )
    (comp (ref "TP17")
      (value "TEST_POINT")
      (footprint "eagle-import:MICRO_MINIATURE")
      (fields (field (name "MPN") "5015") (field (name "MANUFACTURER") "Keystone Electronics"))
      (libsource (lib "eagle-import") (part "TEST_POINT"))
    )
    (comp (ref "TP18")
      (value "TEST_POINT")
      (footprint "eagle-import:MICRO_MINIATURE")
      (fields (field (name "MPN") "5015") (field (name "MANUFACTURER") "Keystone Electronics"))
      (libsource (lib "eagle-import") (part "TEST_POINT"))
    )
    (comp (ref "TP19")
      (value "TEST_POINT")
      (footprint "eagle-import:MICRO_MINIATURE")
      (fields (field (name "MPN") "5015") (field (name "MANUFACTURER") "Keystone Electronics"))
      (libsource (lib "eagle-import") (part "TEST_POINT"))
    )
    (comp (ref "TP20")
      (value "TEST_POINT")
      (footprint "eagle-import:MICRO_MINIATURE")
      (fields (field (name "MPN") "5015") (field (name "MANUFACTURER") "Keystone Electronics"))
      (libsource (lib "eagle-import") (part "TEST_POINT"))
    )
    (comp (ref "TP21")
      (value "TEST_POINT")
      (footprint "eagle-import:MICRO_MINIATURE")
      (fields (field (name "MPN") "5015") (field (name "MANUFACTURER") "Keystone Electronics"))
      (libsource (lib "eagle-import") (part "TEST_POINT"))
    )
    (comp (ref "TP22")
      (value "TEST_POINT")
      (footprint "eagle-import:MICRO_MINIATURE")
      (fields (field (name "MPN") "5015") (field (name "MANUFACTURER") "Keystone Electronics"))
      (libsource (lib "eagle-import") (part "TEST_POINT"))
    )
    (comp (ref "U4")
      (value "VOLTAGE_REGULATOR_SOT223_5V")
      (footprint "eagle-import:SOT223")
      (fields (field (name "MANUFACTURER") "STMicroelectronics") (field (name "MPN") "LDL1117S50R"))
      (libsource (lib "eagle-import") (part "VOLTAGE_REGULATOR_?_SOT2235V"))
    )
    (comp (ref "U100")
      (value "LTC6994-2")
      (footprint "eagle-import:SOT-23-6")
      (libsource (lib "eagle-import") (part "LTC6994-2"))
    )
    (comp (ref "C2")
      (value "CAPACITOR_2220_630V_0.1UF")
      (footprint "eagle-import:2220-CAP")
      (fields
        (field (name "CAPACITANCE") "0.1uF")
        (field (name "MANUFACTURER") "TDK Coporation")
        (field (name "MPN") "C5750CH2J104K280KC")
        (field (name "TOLERANCE") "10%")
        (field (name "VOLTAGE") "630V")
      )
      (libsource (lib "eagle-import") (part "CAPACITOR_?_2220630V_0.1UF"))
    )
    (comp (ref "C3")
      (value "CAPACITOR_2220_630V_1UF")
      (footprint "eagle-import:2220-CAP")
      (fields
        (field (name "CAPACITANCE") "1µF")
        (field (name "MANUFACTURER") "Knowles Syfer")
        (field (name "MPN") "2220Y6300105KXTWS2")
        (field (name "TOLERANCE") "10%")
        (field (name "VOLTAGE") "630V")
      )
      (libsource (lib "eagle-import") (part "CAPACITOR_?_2220630V_1UF"))
    )
    (comp (ref "C4")
      (value "CAPACITOR_1206_250V_0.1UF")
      (footprint "eagle-import:1206-CAP")
      (fields
        (field (name "CAPACITANCE") "0.1uF")
        (field (name "MANUFACTURER") "TDK Corporation")
        (field (name "MPN") "C3216X7R2E104K160AM")
        (field (name "TOLERANCE") "10%")
        (field (name "VOLTAGE") "250V")
      )
      (libsource (lib "eagle-import") (part "CAPACITOR_?_1206250V_0.1UF"))
    )
    (comp (ref "C5")
      (value "CAPACITOR_2220_250V_1UF")
      (footprint "eagle-import:2220-CAP")
      (fields
        (field (name "CAPACITANCE") "1µF")
        (field (name "MANUFACTURER") "TDK Corporation")
        (field (name "MPN") "C5750X7R2E105K230KA")
        (field (name "TOLERANCE") "10%")
        (field (name "VOLTAGE") "250V")
      )
      (libsource (lib "eagle-import") (part "CAPACITOR_?_2220250V_1UF"))
    )
    (comp (ref "C7")
      (value "CAPACITOR_0603_10V_10NF")
      (footprint "eagle-import:0603-CAP")
      (fields
        (field (name "CAPACITANCE") "10nF")
        (field (name "MANUFACTURER") "Yageo")
        (field (name "MPN") "CC0603KRX7R6BB103")
        (field (name "TOLERANCE") "10%")
        (field (name "VOLTAGE") "10V")
      )
      (libsource (lib "eagle-import") (part "CAPACITOR_?_060310V_10NF"))
    )
    (comp (ref "C8")
      (value "CAPACITOR_2220_250V_1UF")
      (footprint "eagle-import:2220-CAP")
      (fields
        (field (name "CAPACITANCE") "1µF")
        (field (name "MANUFACTURER") "TDK Corporation")
        (field (name "MPN") "C5750X7R2E105K230KA")
        (field (name "TOLERANCE") "10%")
        (field (name "VOLTAGE") "250V")
      )
      (libsource (lib "eagle-import") (part "CAPACITOR_?_2220250V_1UF"))
    )
    (comp (ref "C11")
      (value "CAPACITOR_1206_250V_0.1UF")
      (footprint "eagle-import:1206-CAP")
      (fields
        (field (name "CAPACITANCE") "0.1uF")
        (field (name "MANUFACTURER") "TDK Corporation")
        (field (name "MPN") "C3216X7R2E104K160AM")
        (field (name "TOLERANCE") "10%")
        (field (name "VOLTAGE") "250V")
      )
      (libsource (lib "eagle-import") (part "CAPACITOR_?_1206250V_0.1UF"))
    )
    (comp (ref "C12")
      (value "CAPACITOR_0805_25V_22UF")
      (footprint "eagle-import:0805-CAP")
      (fields
        (field (name "CAPACITANCE") "22µF")
        (field (name "MANUFACTURER") "Yageo")
        (field (name "MPN") "CC0805MKX5R8BB226")
        (field (name "TOLERANCE") "20%")
        (field (name "VOLTAGE") "25V")
      )
      (libsource (lib "eagle-import") (part "CAPACITOR_?_080525V_22UF"))
    )
    (comp (ref "C13")
      (value "CAPACITOR_0603_25V_1UF")
      (footprint "eagle-import:0603-CAP")
      (fields
        (field (name "CAPACITANCE") "1µF")
        (field (name "MANUFACTURER") "Samsung Electro-Mechanics")
        (field (name "MPN") "CL10B105KA8NNNC")
        (field (name "TOLERANCE") "10%")
        (field (name "VOLTAGE") "25V")
      )
      (libsource (lib "eagle-import") (part "CAPACITOR_?_060325V_1UF"))
    )
    (comp (ref "C14")
      (value "CAPACITOR_0603_25V_0.1UF")
      (footprint "eagle-import:0603-CAP")
      (fields
        (field (name "CAPACITANCE") "0.1µF")
        (field (name "MANUFACTURER") "Samsung Electro-Mechanics")
        (field (name "MPN") "CL10B104KA8NNNC")
        (field (name "TOLERANCE") "10%")
        (field (name "VOLTAGE") "25V")
      )
      (libsource (lib "eagle-import") (part "CAPACITOR_?_060325V_0.1UF"))
    )
    (comp (ref "C15")
      (value "CAPACITOR_0603_10V_10NF")
      (footprint "eagle-import:0603-CAP")
      (fields
        (field (name "CAPACITANCE") "10nF")
        (field (name "MANUFACTURER") "Yageo")
        (field (name "MPN") "CC0603KRX7R6BB103")
        (field (name "TOLERANCE") "10%")
        (field (name "VOLTAGE") "10V")
      )
      (libsource (lib "eagle-import") (part "CAPACITOR_?_060310V_10NF"))
    )
    (comp (ref "C16")
      (value "CAPACITOR_0603_10V_10NF")
      (footprint "eagle-import:0603-CAP")
      (fields
        (field (name "CAPACITANCE") "10nF")
        (field (name "MANUFACTURER") "Yageo")
        (field (name "MPN") "CC0603KRX7R6BB103")
        (field (name "TOLERANCE") "10%")
        (field (name "VOLTAGE") "10V")
      )
      (libsource (lib "eagle-import") (part "CAPACITOR_?_060310V_10NF"))
    )
    (comp (ref "C17")
      (value "CAPACITOR_0603_10V_1UF")
      (footprint "eagle-import:0603-CAP")
      (fields
        (field (name "CAPACITANCE") "1µF")
        (field (name "MANUFACTURER") "Yageo")
        (field (name "MPN") "CC0603KRX7R6BB105")
        (field (name "TOLERANCE") "10%")
        (field (name "VOLTAGE") "10V")
      )
      (libsource (lib "eagle-import") (part "CAPACITOR_?_060310V_1UF"))
    )
    (comp (ref "C18")
      (value "CAPACITOR_0603_10V_1UF")
      (footprint "eagle-import:0603-CAP")
      (fields
        (field (name "CAPACITANCE") "1µF")
        (field (name "MANUFACTURER") "Yageo")
        (field (name "MPN") "CC0603KRX7R6BB105")
        (field (name "TOLERANCE") "10%")
        (field (name "VOLTAGE") "10V")
      )
      (libsource (lib "eagle-import") (part "CAPACITOR_?_060310V_1UF"))
    )
    (comp (ref "C19")
      (value "CAPACITOR_0603_10V_1UF")
      (footprint "eagle-import:0603-CAP")
      (fields
        (field (name "CAPACITANCE") "1µF")
        (field (name "MANUFACTURER") "Yageo")
        (field (name "MPN") "CC0603KRX7R6BB105")
        (field (name "TOLERANCE") "10%")
        (field (name "VOLTAGE") "10V")
      )
      (libsource (lib "eagle-import") (part "CAPACITOR_?_060310V_1UF"))
    )
    (comp (ref "C20")
      (value "CAPACITOR_0603_10V_1UF")
      (footprint "eagle-import:0603-CAP")
      (fields
        (field (name "CAPACITANCE") "1µF")
        (field (name "MANUFACTURER") "Yageo")
        (field (name "MPN") "CC0603KRX7R6BB105")
        (field (name "TOLERANCE") "10%")
        (field (name "VOLTAGE") "10V")
      )
      (libsource (lib "eagle-import") (part "CAPACITOR_?_060310V_1UF"))
    )
    (comp (ref "C21")
      (value "CAPACITOR_0603_10V_1UF")
      (footprint "eagle-import:0603-CAP")
      (fields
        (field (name "CAPACITANCE") "1µF")
        (field (name "MANUFACTURER") "Yageo")
        (field (name "MPN") "CC0603KRX7R6BB105")
        (field (name "TOLERANCE") "10%")
        (field (name "VOLTAGE") "10V")
      )
      (libsource (lib "eagle-import") (part "CAPACITOR_?_060310V_1UF"))
    )
    (comp (ref "C22")
      (value "CAPACITOR_0603_10V_1UF")
      (footprint "eagle-import:0603-CAP")
      (fields
        (field (name "CAPACITANCE") "1µF")
        (field (name "MANUFACTURER") "Yageo")
        (field (name "MPN") "CC0603KRX7R6BB105")
        (field (name "TOLERANCE") "10%")
        (field (name "VOLTAGE") "10V")
      )
      (libsource (lib "eagle-import") (part "CAPACITOR_?_060310V_1UF"))
    )
    (comp (ref "C102")
      (value "CAPACITOR_0603_10V_0.1UF")
      (footprint "eagle-import:0603-CAP")
      (fields
        (field (name "CAPACITANCE") "0.1µF")
        (field (name "MANUFACTURER") "Vishay Vitramon")
        (field (name "MPN") "VJ0603Y104JXQPW1BC")
        (field (name "TOLERANCE") "5%")
        (field (name "VOLTAGE") "10V")
      )
      (libsource (lib "eagle-import") (part "CAPACITOR_?_060310V_0.1UF"))
    )
    (comp (ref "C103")
      (value "CAPACITOR_0603_10V_1UF")
      (footprint "eagle-import:0603-CAP")
      (fields
        (field (name "CAPACITANCE") "1µF")
        (field (name "MANUFACTURER") "Yageo")
        (field (name "MPN") "CC0603KRX7R6BB105")
        (field (name "TOLERANCE") "10%")
        (field (name "VOLTAGE") "10V")
      )
      (libsource (lib "eagle-import") (part "CAPACITOR_?_060310V_1UF"))
    )
    (comp (ref "C107")
      (value "CAPACITOR_0603_10V_1UF")
      (footprint "eagle-import:0603-CAP")
      (fields
        (field (name "CAPACITANCE") "1µF")
        (field (name "MANUFACTURER") "Yageo")
        (field (name "MPN") "CC0603KRX7R6BB105")
        (field (name "TOLERANCE") "10%")
        (field (name "VOLTAGE") "10V")
      )
      (libsource (lib "eagle-import") (part "CAPACITOR_?_060310V_1UF"))
    )
    (comp (ref "C108")
      (value "CAPACITOR_0603_10V_0.1UF")
      (footprint "eagle-import:0603-CAP")
      (fields
        (field (name "CAPACITANCE") "0.1µF")
        (field (name "MANUFACTURER") "Vishay Vitramon")
        (field (name "MPN") "VJ0603Y104JXQPW1BC")
        (field (name "TOLERANCE") "5%")
        (field (name "VOLTAGE") "10V")
      )
      (libsource (lib "eagle-import") (part "CAPACITOR_?_060310V_0.1UF"))
    )
    (comp (ref "C109")
      (value "CAPACITOR_2220_250V_1UF")
      (footprint "eagle-import:2220-CAP")
      (fields
        (field (name "CAPACITANCE") "1µF")
        (field (name "MANUFACTURER") "TDK Corporation")
        (field (name "MPN") "C5750X7R2E105K230KA")
        (field (name "TOLERANCE") "10%")
        (field (name "VOLTAGE") "250V")
      )
      (libsource (lib "eagle-import") (part "CAPACITOR_?_2220250V_1UF"))
    )
    (comp (ref "D3")
      (value "SCHOTTKY_SOD323_30V")
      (footprint "eagle-import:SOD-323")
      (fields
        (field (name "MANUFACTURER") "Toshiba Semiconductor and Storage")
        (field (name "MPN") "CUS08F30")
        (field (name "VOLTAGE") "30V")
      )
      (libsource (lib "eagle-import") (part "SCHOTTKY_?_SOD32330V"))
    )
    (comp (ref "D4")
      (value "LED_0603_BLUE")
      (footprint "eagle-import:0603-LED")
      (fields
        (field (name "COLOR") "Blue")
        (field (name "MANUFACTURER") "Kingbright")
        (field (name "MPN") "APT1608VBC/D")
      )
      (libsource (lib "eagle-import") (part "LED_?_0603BLUE"))
    )
    (comp (ref "D102")
      (value "RECTIFIER_400V_SOD123")
      (footprint "eagle-import:SOD123F")
      (fields
        (field (name "MANUFACTURER") "Diodes Incorporated")
        (field (name "MPN") "US1GWF-7")
        (field (name "VOLTAGE") "400V")
      )
      (libsource (lib "eagle-import") (part "RECTIFIER__?SOD123400V"))
    )
    (comp (ref "L3")
      (value "INDUCTOR_SRU1048_330UH")
      (footprint "eagle-import:SRU1048")
      (fields
        (field (name "INDUCTANCE") "330µH")
        (field (name "MANUFACTURER") "Bourns Inc.")
        (field (name "MPN") "SRU1048-331Y")
        (field (name "TOLERANCE") "30%")
      )
      (libsource (lib "eagle-import") (part "INDUCTOR_?_SRU1048330UH"))
    )
    (comp (ref "R2")
      (value "RESISTOR_0603_39")
      (footprint "eagle-import:0603-RES")
      (fields
        (field (name "MANUFACTURER") "Yageo")
        (field (name "MPN") "RT0603BRD0739RL")
        (field (name "POWER") "0.1W")
        (field (name "RESISTANCE") "39")
      )
      (libsource (lib "eagle-import") (part "RESISTOR_?_060339"))
    )
    (comp (ref "R5")
      (value "RESISTOR_0603_10K")
      (footprint "eagle-import:0603-RES")
      (fields
        (field (name "MANUFACTURER") "Yageo")
        (field (name "MPN") "RC0603FR-0710KL")
        (field (name "POWER") "0.1W")
        (field (name "RESISTANCE") "10k")
      )
      (libsource (lib "eagle-import") (part "RESISTOR_?_060310K"))
    )
    (comp (ref "R6")
      (value "RESISTOR_0603_1K")
      (footprint "eagle-import:0603-RES")
      (fields
        (field (name "MANUFACTURER") "Yageo")
        (field (name "MPN") "RC0603FR-071KL")
        (field (name "POWER") "0.1W")
        (field (name "RESISTANCE") "1k")
      )
      (libsource (lib "eagle-import") (part "RESISTOR_?_06031K"))
    )
    (comp (ref "R11")
      (value "RESISTOR_0603_HV750K")
      (footprint "eagle-import:0603-RES")
      (fields
        (field (name "MANUFACTURER") "Rohm")
        (field (name "MPN") "KTR03EZPF7502")
        (field (name "POWER") "0.1W")
        (field (name "RESISTANCE") "750k")
      )
      (libsource (lib "eagle-import") (part "RESISTOR_?_0603HV750K"))
    )
    (comp (ref "R12")
      (value "RESISTOR_0603_HV750K")
      (footprint "eagle-import:0603-RES")
      (fields
        (field (name "MANUFACTURER") "Rohm")
        (field (name "MPN") "KTR03EZPF7502")
        (field (name "POWER") "0.1W")
        (field (name "RESISTANCE") "750k")
      )
      (libsource (lib "eagle-import") (part "RESISTOR_?_0603HV750K"))
    )
    (comp (ref "R14")
      (value "RESISTOR_0603_360K")
      (footprint "eagle-import:0603-RES")
      (fields
        (field (name "MANUFACTURER") "Rohm Semiconductor")
        (field (name "MPN") "KTR03EZPF3603")
        (field (name "POWER") "0.1W")
        (field (name "RESISTANCE") "360k")
      )
      (libsource (lib "eagle-import") (part "RESISTOR_?_0603360K"))
    )
    (comp (ref "R15")
      (value "RESISTOR_0603_360K")
      (footprint "eagle-import:0603-RES")
      (fields
        (field (name "MANUFACTURER") "Rohm Semiconductor")
        (field (name "MPN") "KTR03EZPF3603")
        (field (name "POWER") "0.1W")
        (field (name "RESISTANCE") "360k")
      )
      (libsource (lib "eagle-import") (part "RESISTOR_?_0603360K"))
    )
    (comp (ref "R16")
      (value "RESISTOR_0603_HV75K")
      (footprint "eagle-import:0603-RES")
      (fields
        (field (name "MANUFACTURER") "Rohm")
        (field (name "MPN") "KTR03EZPF7503")
        (field (name "POWER") "0.1W")
        (field (name "RESISTANCE") "75k")
      )
      (libsource (lib "eagle-import") (part "RESISTOR_?_0603HV75K"))
    )
    (comp (ref "R17")
      (value "RESISTOR_0603_HV75K")
      (footprint "eagle-import:0603-RES")
      (fields
        (field (name "MANUFACTURER") "Rohm")
        (field (name "MPN") "KTR03EZPF7503")
        (field (name "POWER") "0.1W")
        (field (name "RESISTANCE") "75k")
      )
      (libsource (lib "eagle-import") (part "RESISTOR_?_0603HV75K"))
    )
    (comp (ref "R18")
      (value "RESISTOR_0603_HV75K")
      (footprint "eagle-import:0603-RES")
      (fields
        (field (name "MANUFACTURER") "Rohm")
        (field (name "MPN") "KTR03EZPF7503")
        (field (name "POWER") "0.1W")
        (field (name "RESISTANCE") "75k")
      )
      (libsource (lib "eagle-import") (part "RESISTOR_?_0603HV75K"))
    )
    (comp (ref "R19")
      (value "RESISTOR_0603_HV75K")
      (footprint "eagle-import:0603-RES")
      (fields
        (field (name "MANUFACTURER") "Rohm")
        (field (name "MPN") "KTR03EZPF7503")
        (field (name "POWER") "0.1W")
        (field (name "RESISTANCE") "75k")
      )
      (libsource (lib "eagle-import") (part "RESISTOR_?_0603HV75K"))
    )
    (comp (ref "R20")
      (value "RESISTOR_0603_33.2K")
      (footprint "eagle-import:0603-RES")
      (fields
        (field (name "MANUFACTURER") "Panasonic Electronic Components")
        (field (name "MPN") "ERJ-PB3B3322V")
        (field (name "POWER") "0.1W")
        (field (name "RESISTANCE") "33.2k")
      )
      (libsource (lib "eagle-import") (part "RESISTOR_?_060333.2K"))
    )
    (comp (ref "R21")
      (value "RESISTOR_0603_33.2K")
      (footprint "eagle-import:0603-RES")
      (fields
        (field (name "MANUFACTURER") "Panasonic Electronic Components")
        (field (name "MPN") "ERJ-PB3B3322V")
        (field (name "POWER") "0.1W")
        (field (name "RESISTANCE") "33.2k")
      )
      (libsource (lib "eagle-import") (part "RESISTOR_?_060333.2K"))
    )
    (comp (ref "R107")
      (value "RESISTOR_0603_75K")
      (footprint "eagle-import:0603-RES")
      (fields
        (field (name "MANUFACTURER") "Yageo")
        (field (name "MPN") "RT0603BRE0775KL")
        (field (name "POWER") "0.1W")
        (field (name "RESISTANCE") "75k")
      )
      (libsource (lib "eagle-import") (part "RESISTOR_?_060375K"))
    )
    (comp (ref "R108")
      (value "RESISTOR_0603_8.35K")
      (footprint "eagle-import:0603-RES")
      (fields
        (field (name "MANUFACTURER") "Vishay Dale Thin Film")
        (field (name "MPN") "PTN0603E8351BST1")
        (field (name "POWER") "0.15W")
        (field (name "RESISTANCE") "8.35k")
      )
      (libsource (lib "eagle-import") (part "RESISTOR_?_06038.35K"))
    )
    (comp (ref "R109")
      (value "RESISTOR_0603_13.3K")
      (footprint "eagle-import:0603-RES")
      (fields
        (field (name "MANUFACTURER") "Panasonic Electronic Components")
        (field (name "MPN") "ERJ-PB3B1332V")
        (field (name "POWER") "0.2W")
        (field (name "RESISTANCE") "13.3k")
      )
      (libsource (lib "eagle-import") (part "RESISTOR_?_060313.3K"))
    )
    (comp (ref "R110")
      (value "RESISTOR_0805_976K")
      (footprint "eagle-import:0805-RES")
      (fields
        (field (name "MANUFACTURER") "Panasonic Electronic Components")
        (field (name "MPN") "  ERJ-PB6B9763V")
        (field (name "POWER") "0.25W")
        (field (name "RESISTANCE") "976k")
      )
      (libsource (lib "eagle-import") (part "RESISTOR_?_0805976K"))
    )
    (comp (ref "R112")
      (value "RESISTOR_0805_HV365K")
      (footprint "eagle-import:0805-RES")
      (fields
        (field (name "MANUFACTURER") "Rohm")
        (field (name "MPN") "KTR10EZPF3653")
        (field (name "POWER") "0.125W")
        (field (name "RESISTANCE") "365k")
      )
      (libsource (lib "eagle-import") (part "RESISTOR_?_0805HV365K"))
    )
    (comp (ref "R113")
      (value "RESISTOR_0603_3.32K")
      (footprint "eagle-import:0603-RES")
      (fields
        (field (name "MANUFACTURER") "Yageo")
        (field (name "MPN") "RT0603BRD073K32L")
        (field (name "POWER") "0.1W")
        (field (name "RESISTANCE") "3.32k")
      )
      (libsource (lib "eagle-import") (part "RESISTOR_?_06033.32K"))
    )
    (comp (ref "TP9")
      (value "TEST_POINT")
      (footprint "eagle-import:MICRO_MINIATURE")
      (fields (field (name "MPN") "5015") (field (name "MANUFACTURER") "Keystone Electronics"))
      (libsource (lib "eagle-import") (part "TEST_POINT"))
    )
    (comp (ref "TP12")
      (value "TEST_POINT")
      (footprint "eagle-import:MICRO_MINIATURE")
      (fields (field (name "MPN") "5015") (field (name "MANUFACTURER") "Keystone Electronics"))
      (libsource (lib "eagle-import") (part "TEST_POINT"))
    )
    (comp (ref "TP13")
      (value "TEST_POINT")
      (footprint "eagle-import:MICRO_MINIATURE")
      (fields (field (name "MPN") "5015") (field (name "MANUFACTURER") "Keystone Electronics"))
      (libsource (lib "eagle-import") (part "TEST_POINT"))
    )
    (comp (ref "U1")
      (value "LTC3639")
      (footprint "eagle-import:MSE16(12)")
      (fields (field (name "MPN") "LTC3639EMSE#TRPBF ") (field (name "MANUFACTURER") "Analog Devices Inc."))
      (libsource (lib "eagle-import") (part "LTC3639"))
    )
    (comp (ref "U2")
      (value "ISO224B_AIRGAP")
      (footprint "eagle-import:SOIC-08(WIDE,0.295_)-AIRGAP")
      (fields (field (name "MANUFACTURER") "Texas Instruments") (field (name "MPN") "ISO224BDWVR"))
      (libsource (lib "eagle-import") (part "ISO224_AIRGAPB"))
    )
    (comp (ref "U3")
      (value "ISO224B_AIRGAP")
      (footprint "eagle-import:SOIC-08(WIDE,0.295_)-AIRGAP")
      (fields (field (name "MANUFACTURER") "Texas Instruments") (field (name "MPN") "ISO224BDWVR"))
      (libsource (lib "eagle-import") (part "ISO224_AIRGAPB"))
    )
    (comp (ref "U102")
      (value "VOLTAGE_REGULATOR_ADJ_LR8_DPAK")
      (footprint "eagle-import:DPAK(2-7K1S)")
      (fields (field (name "MANUFACTURER") "Microchip Technology") (field (name "MPN") "LR8K4-G"))
      (libsource (lib "eagle-import") (part "VOLTAGE_REGULATOR_ADJ__?DPAKLR8"))
    )
  )
  (nets
    (net (code "1") (name "+5V") (class "Default")
      (node (ref "C101") (pin "1") (pinfunction "1_1") (pintype "passive"))
      (node (ref "C102") (pin "1") (pinfunction "1_1") (pintype "passive"))
      (node (ref "C103") (pin "1") (pinfunction "1_1") (pintype "passive"))
      (node (ref "C105") (pin "1") (pinfunction "1_1") (pintype "passive"))
      (node (ref "C107") (pin "1") (pinfunction "1_1") (pintype "passive"))
      (node (ref "C108") (pin "1") (pinfunction "1_1") (pintype "passive"))
      (node (ref "C23") (pin "1") (pinfunction "1_1") (pintype "passive"))
      (node (ref "R105") (pin "2") (pinfunction "2_2") (pintype "passive"))
      (node (ref "R26") (pin "1") (pinfunction "1_1") (pintype "passive"))
      (node (ref "TP20") (pin "1") (pinfunction "P$1_1") (pintype "passive"))
      (node (ref "U101") (pin "5") (pinfunction "V+_5") (pintype "power_in"))
      (node (ref "U2") (pin "8") (pinfunction "VDD2_8") (pintype "power_in"))
      (node (ref "U3") (pin "8") (pinfunction "VDD2_8") (pintype "power_in"))
      (node (ref "U4") (pin "2") (pinfunction "OUT_2") (pintype "power_in"))
      (node (ref "U4") (pin "4") (pinfunction "OUT_4") (pintype "power_in"))
    )
    (net (code "2") (name "+12V") (class "Default")
      (node (ref "C100") (pin "1") (pinfunction "1_1") (pintype "passive"))
      (node (ref "C104") (pin "1") (pinfunction "1_1") (pintype "passive"))
      (node (ref "J4") (pin "1") (pinfunction "1_1") (pintype "passive"))
      (node (ref "R25") (pin "2") (pinfunction "2_2") (pintype "passive"))
      (node (ref "TP19") (pin "1") (pinfunction "P$1_1") (pintype "passive"))
      (node (ref "U4") (pin "3") (pinfunction "IN_3") (pintype "power_in"))
    )
    (net (code "3") (name "DCDC+") (class "Default")
      (node (ref "J1") (pin "1") (pinfunction "1_1") (pintype "passive"))
      (node (ref "J1") (pin "3") (pinfunction "3_3") (pintype "passive"))
      (node (ref "R1") (pin "2") (pinfunction "2_2") (pintype "passive"))
      (node (ref "TP1") (pin "1") (pinfunction "P$1_1") (pintype "passive"))
      (node (ref "XF1") (pin "3") (pinfunction "2_3") (pintype "passive"))
      (node (ref "XF1") (pin "4") (pinfunction "2_4") (pintype "passive"))
    )
    (net (code "4") (name "DCDC-") (class "Default")
      (node (ref "C1") (pin "-") (pinfunction "MINUS_-") (pintype "passive"))
      (node (ref "C110") (pin "1") (pinfunction "1_1") (pintype "passive"))
      (node (ref "C111") (pin "1") (pinfunction "1_1") (pintype "passive"))
      (node (ref "C112") (pin "1") (pinfunction "1_1") (pintype "passive"))
      (node (ref "D1") (pin "1") (pinfunction "C_1") (pintype "passive"))
      (node (ref "J1") (pin "2") (pinfunction "2_2") (pintype "passive"))
      (node (ref "J1") (pin "4") (pinfunction "4_4") (pintype "passive"))
      (node (ref "TP2") (pin "1") (pinfunction "P$1_1") (pintype "passive"))
      (node (ref "U103") (pin "7") (pinfunction "-OUT_7") (pintype "power_in"))
      (node (ref "U103") (pin "9") (pinfunction "-OUT_9") (pintype "power_in"))
    )
    (net (code "5") (name "DCDC_ENABLE") (class "Default")
      (node (ref "D5") (pin "3") (pinfunction "C_3") (pintype "passive"))
      (node (ref "R23") (pin "2") (pinfunction "2_2") (pintype "passive"))
      (node (ref "R24") (pin "1") (pinfunction "1_1") (pintype "passive"))
      (node (ref "R28") (pin "2") (pinfunction "2_2") (pintype "passive"))
      (node (ref "U100") (pin "4") (pinfunction "OUT_4") (pintype "bidirectional"))
      (node (ref "U101") (pin "1") (pinfunction "IN_1") (pintype "bidirectional"))
    )
    (net (code "6") (name "ENABLE") (class "Default")
      (node (ref "K100") (pin "4") (pinfunction "CONTACT2_4") (pintype "bidirectional"))
      (node (ref "U103") (pin "3") (pinfunction "EN_3") (pintype "input"))
    )
    (net (code "7") (name "GND") (class "Default")
      (node (ref "C100") (pin "2") (pinfunction "2_2") (pintype "passive"))
      (node (ref "C101") (pin "2") (pinfunction "2_2") (pintype "passive"))
      (node (ref "C102") (pin "2") (pinfunction "2_2") (pintype "passive"))
      (node (ref "C103") (pin "2") (pinfunction "2_2") (pintype "passive"))
      (node (ref "C104") (pin "2") (pinfunction "2_2") (pintype "passive"))
      (node (ref "C105") (pin "2") (pinfunction "2_2") (pintype "passive"))
      (node (ref "C106") (pin "2") (pinfunction "2_2") (pintype "passive"))
      (node (ref "C107") (pin "2") (pinfunction "2_2") (pintype "passive"))
      (node (ref "C108") (pin "2") (pinfunction "2_2") (pintype "passive"))
      (node (ref "C23") (pin "2") (pinfunction "2_2") (pintype "passive"))
      (node (ref "D10") (pin "1") (pinfunction "C_1") (pintype "passive"))
      (node (ref "D100") (pin "A") (pinfunction "A_A") (pintype "passive"))
      (node (ref "D11") (pin "1") (pinfunction "C_1") (pintype "passive"))
      (node (ref "D5") (pin "1") (pinfunction "A_1") (pintype "passive"))
      (node (ref "D6") (pin "1") (pinfunction "C_1") (pintype "passive"))
      (node (ref "D7") (pin "1") (pinfunction "C_1") (pintype "passive"))
      (node (ref "D8") (pin "1") (pinfunction "C_1") (pintype "passive"))
      (node (ref "D9") (pin "1") (pinfunction "C_1") (pintype "passive"))
      (node (ref "J4") (pin "4") (pinfunction "4_4") (pintype "passive"))
      (node (ref "K100") (pin "2") (pinfunction "CONTROL-_2") (pintype "passive"))
      (node (ref "K2") (pin "3") (pinfunction "COIL-_3") (pintype "bidirectional"))
      (node (ref "K3") (pin "2") (pinfunction "CONTROL-_2") (pintype "passive"))
      (node (ref "Q1") (pin "2") (pinfunction "S_2") (pintype "passive"))
      (node (ref "R100") (pin "1") (pinfunction "1_1") (pintype "passive"))
      (node (ref "R101") (pin "1") (pinfunction "1_1") (pintype "passive"))
      (node (ref "R103") (pin "1") (pinfunction "1_1") (pintype "passive"))
      (node (ref "R104") (pin "1") (pinfunction "1_1") (pintype "passive"))
      (node (ref "R23") (pin "1") (pinfunction "1_1") (pintype "passive"))
      (node (ref "TP22") (pin "1") (pinfunction "P$1_1") (pintype "passive"))
      (node (ref "U100") (pin "6") (pinfunction "DIV_6") (pintype "bidirectional"))
      (node (ref "U101") (pin "2") (pinfunction "GND_2") (pintype "power_in"))
      (node (ref "U2") (pin "5") (pinfunction "GND2_5") (pintype "power_in"))
      (node (ref "U3") (pin "5") (pinfunction "GND2_5") (pintype "power_in"))
      (node (ref "U4") (pin "1") (pinfunction "GND_1") (pintype "power_in"))
    )
    (net (code "8") (name "IP+") (class "Default")
      (node (ref "J4") (pin "5") (pinfunction "5_5") (pintype "passive"))
      (node (ref "TP15") (pin "1") (pinfunction "P$1_1") (pintype "passive"))
      (node (ref "U3") (pin "7") (pinfunction "OUTP_7") (pintype "output"))
    )
    (net (code "9") (name "IP-") (class "Default")
      (node (ref "J4") (pin "6") (pinfunction "6_6") (pintype "passive"))
      (node (ref "TP14") (pin "1") (pinfunction "P$1_1") (pintype "passive"))
      (node (ref "U3") (pin "6") (pinfunction "OUTN_6") (pintype "output"))
    )
    (net (code "10") (name "IT+") (class "Default")
      (node (ref "J4") (pin "7") (pinfunction "7_7") (pintype "passive"))
      (node (ref "TP16") (pin "1") (pinfunction "P$1_1") (pintype "passive"))
      (node (ref "U2") (pin "7") (pinfunction "OUTP_7") (pintype "output"))
    )
    (net (code "11") (name "IT-") (class "Default")
      (node (ref "J4") (pin "8") (pinfunction "8_8") (pintype "passive"))
      (node (ref "TP17") (pin "1") (pinfunction "P$1_1") (pintype "passive"))
      (node (ref "U2") (pin "6") (pinfunction "OUTN_6") (pintype "output"))
    )
    (net (code "12") (name "LED+") (class "Default")
      (node (ref "J2") (pin "3") (pinfunction "3_3") (pintype "passive"))
      (node (ref "R9") (pin "2") (pinfunction "2_2") (pintype "passive"))
    )
    (net (code "13") (name "LR8_O") (class "Default")
      (node (ref "C4") (pin "1") (pinfunction "1_1") (pintype "passive"))
      (node (ref "C5") (pin "1") (pinfunction "1_1") (pintype "passive"))
      (node (ref "D102") (pin "A") (pinfunction "A_A") (pintype "passive"))
      (node (ref "D3") (pin "A") (pinfunction "A_A") (pintype "passive"))
      (node (ref "R113") (pin "2") (pinfunction "2_2") (pintype "passive"))
      (node (ref "R5") (pin "1") (pinfunction "1_1") (pintype "passive"))
      (node (ref "TP9") (pin "1") (pinfunction "P$1_1") (pintype "passive"))
      (node (ref "U102") (pin "2") (pinfunction "OUT_2") (pintype "power_in"))
    )
    (net (code "14") (name "Net-(C1-PLUS)") (class "Default")
      (node (ref "C1") (pin "+") (pinfunction "PLUS_+") (pintype "passive"))
      (node (ref "C110") (pin "2") (pinfunction "2_2") (pintype "passive"))
      (node (ref "C111") (pin "2") (pinfunction "2_2") (pintype "passive"))
      (node (ref "C112") (pin "2") (pinfunction "2_2") (pintype "passive"))
      (node (ref "U103") (pin "6") (pinfunction "+OUT_6") (pintype "power_in"))
      (node (ref "U103") (pin "8") (pinfunction "+OUT_8") (pintype "power_in"))
      (node (ref "XF1") (pin "1") (pinfunction "1_1") (pintype "passive"))
      (node (ref "XF1") (pin "2") (pinfunction "1_2") (pintype "passive"))
    )
    (net (code "15") (name "Net-(C7-Pad2)") (class "Default")
      (node (ref "C7") (pin "2") (pinfunction "2_2") (pintype "passive"))
      (node (ref "R5") (pin "2") (pinfunction "2_2") (pintype "passive"))
    )
    (net (code "16") (name "Net-(D1-A)") (class "Default")
      (node (ref "D1") (pin "2") (pinfunction "A_2") (pintype "passive"))
      (node (ref "R1") (pin "1") (pinfunction "1_1") (pintype "passive"))
    )
    (net (code "17") (name "Net-(D2-A)") (class "Default")
      (node (ref "D2") (pin "2") (pinfunction "A_2") (pintype "passive"))
      (node (ref "R4") (pin "2") (pinfunction "2_2") (pintype "passive"))
    )
    (net (code "18") (name "Net-(D4-A)") (class "Default")
      (node (ref "D4") (pin "2") (pinfunction "A_2") (pintype "passive"))
      (node (ref "R6") (pin "1") (pinfunction "1_1") (pintype "passive"))
    )
    (net (code "19") (name "Net-(D6-A)") (class "Default")
      (node (ref "D6") (pin "2") (pinfunction "A_2") (pintype "passive"))
      (node (ref "R25") (pin "1") (pinfunction "1_1") (pintype "passive"))
    )
    (net (code "20") (name "Net-(D7-A)") (class "Default")
      (node (ref "D7") (pin "2") (pinfunction "A_2") (pintype "passive"))
      (node (ref "R27") (pin "1") (pinfunction "1_1") (pintype "passive"))
    )
    (net (code "21") (name "Net-(D8-A)") (class "Default")
      (node (ref "D8") (pin "2") (pinfunction "A_2") (pintype "passive"))
      (node (ref "R28") (pin "1") (pinfunction "1_1") (pintype "passive"))
    )
    (net (code "22") (name "Net-(D9-A)") (class "Default")
      (node (ref "D9") (pin "2") (pinfunction "A_2") (pintype "passive"))
      (node (ref "R26") (pin "2") (pinfunction "2_2") (pintype "passive"))
    )
    (net (code "23") (name "Net-(D10-A)") (class "Default")
      (node (ref "D10") (pin "2") (pinfunction "A_2") (pintype "passive"))
      (node (ref "R29") (pin "1") (pinfunction "1_1") (pintype "passive"))
    )
    (net (code "24") (name "Net-(D11-A)") (class "Default")
      (node (ref "D11") (pin "2") (pinfunction "A_2") (pintype "passive"))
      (node (ref "R30") (pin "1") (pinfunction "1_1") (pintype "passive"))
    )
    (net (code "25") (name "Net-(K1-COIL-)") (class "Default")
      (node (ref "D101") (pin "A") (pinfunction "A_A") (pintype "passive"))
      (node (ref "K1") (pin "3") (pinfunction "COIL-_3") (pintype "bidirectional"))
      (node (ref "Q1") (pin "3") (pinfunction "D_3") (pintype "passive"))
    )
    (net (code "26") (name "Net-(K1-CONTACT2)") (class "Default")
      (node (ref "K1") (pin "4") (pinfunction "CONTACT2_4") (pintype "bidirectional"))
      (node (ref "R10") (pin "1") (pinfunction "1_1") (pintype "passive"))
    )
    (net (code "27") (name "Net-(K2-CONTACT2)") (class "Default")
      (node (ref "K2") (pin "4") (pinfunction "CONTACT2_4") (pintype "bidirectional"))
      (node (ref "R13") (pin "2") (pinfunction "2_2") (pintype "passive"))
    )
    (net (code "28") (name "Net-(K3-CONTACT1)") (class "Default")
      (node (ref "K3") (pin "3") (pinfunction "CONTACT1_3") (pintype "bidirectional"))
      (node (ref "R22") (pin "2") (pinfunction "2_2") (pintype "passive"))
    )
    (net (code "29") (name "Net-(K3-CONTROL+)") (class "Default")
      (node (ref "K3") (pin "1") (pinfunction "CONTROL+_1") (pintype "passive"))
      (node (ref "R31") (pin "1") (pinfunction "1_1") (pintype "passive"))
    )
    (net (code "30") (name "Net-(K100-CONTROL+)") (class "Default")
      (node (ref "K100") (pin "1") (pinfunction "CONTROL+_1") (pintype "passive"))
      (node (ref "R106") (pin "2") (pinfunction "2_2") (pintype "passive"))
    )
    (net (code "31") (name "Net-(L1-Pad2)") (class "Default")
      (node (ref "L1") (pin "2") (pinfunction "2_2") (pintype "passive"))
      (node (ref "R3") (pin "1") (pinfunction "1_1") (pintype "passive"))
    )
    (net (code "32") (name "Net-(Q1-G)") (class "Default")
      (node (ref "Q1") (pin "1") (pinfunction "G_1") (pintype "passive"))
      (node (ref "R24") (pin "2") (pinfunction "2_2") (pintype "passive"))
    )
    (net (code "33") (name "Net-(R11-Pad1)") (class "Default")
      (node (ref "R11") (pin "1") (pinfunction "1_1") (pintype "passive"))
      (node (ref "R14") (pin "2") (pinfunction "2_2") (pintype "passive"))
    )
    (net (code "34") (name "Net-(R12-Pad1)") (class "Default")
      (node (ref "R12") (pin "1") (pinfunction "1_1") (pintype "passive"))
      (node (ref "R15") (pin "2") (pinfunction "2_2") (pintype "passive"))
    )
    (net (code "35") (name "Net-(U1-ISET)") (class "Default")
      (node (ref "R107") (pin "2") (pinfunction "2_2") (pintype "passive"))
      (node (ref "U1") (pin "11") (pinfunction "ISET_11") (pintype "bidirectional"))
    )
    (net (code "36") (name "Net-(U1-OVLO)") (class "Default")
      (node (ref "R108") (pin "2") (pinfunction "2_2") (pintype "passive"))
      (node (ref "R109") (pin "1") (pinfunction "1_1") (pintype "passive"))
      (node (ref "U1") (pin "12") (pinfunction "OVLO_12") (pintype "input"))
    )
    (net (code "37") (name "Net-(U1-RUN)") (class "Default")
      (node (ref "R109") (pin "2") (pinfunction "2_2") (pintype "passive"))
      (node (ref "R110") (pin "1") (pinfunction "1_1") (pintype "passive"))
      (node (ref "U1") (pin "14") (pinfunction "RUN_14") (pintype "input"))
    )
    (net (code "38") (name "Net-(U1-SS)") (class "Default")
      (node (ref "U1") (pin "10") (pinfunction "SS_10") (pintype "input"))
      (node (ref "U1") (pin "7") (pinfunction "VPRG1_7") (pintype "input"))
    )
    (net (code "39") (name "Net-(U1-SW)") (class "Default")
      (node (ref "L3") (pin "1") (pinfunction "1_1") (pintype "passive"))
      (node (ref "U1") (pin "1") (pinfunction "SW_1") (pintype "power_in"))
    )
    (net (code "40") (name "Net-(U1-VDD)") (class "Default")
      (node (ref "C109") (pin "1") (pinfunction "1_1") (pintype "passive"))
      (node (ref "C11") (pin "1") (pinfunction "1_1") (pintype "passive"))
      (node (ref "C7") (pin "1") (pinfunction "1_1") (pintype "passive"))
      (node (ref "C8") (pin "1") (pinfunction "1_1") (pintype "passive"))
      (node (ref "D3") (pin "C") (pinfunction "C_C") (pintype "passive"))
      (node (ref "R110") (pin "2") (pinfunction "2_2") (pintype "passive"))
      (node (ref "U1") (pin "3") (pinfunction "VDD_3") (pintype "power_in"))
    )
    (net (code "41") (name "Net-(U2-IN)") (class "Default")
      (node (ref "C16") (pin "1") (pinfunction "1_1") (pintype "passive"))
      (node (ref "R21") (pin "2") (pinfunction "2_2") (pintype "passive"))
      (node (ref "U2") (pin "2") (pinfunction "IN_2") (pintype "input"))
    )
    (net (code "42") (name "Net-(U2-VCAP)") (class "Default")
      (node (ref "C20") (pin "1") (pinfunction "1_1") (pintype "passive"))
      (node (ref "U2") (pin "1") (pinfunction "VCAP_1") (pintype "passive"))
    )
    (net (code "43") (name "Net-(U3-IN)") (class "Default")
      (node (ref "C15") (pin "1") (pinfunction "1_1") (pintype "passive"))
      (node (ref "R20") (pin "2") (pinfunction "2_2") (pintype "passive"))
      (node (ref "U3") (pin "2") (pinfunction "IN_2") (pintype "input"))
    )
    (net (code "44") (name "Net-(U3-VCAP)") (class "Default")
      (node (ref "C19") (pin "1") (pinfunction "1_1") (pintype "passive"))
      (node (ref "U3") (pin "1") (pinfunction "VCAP_1") (pintype "passive"))
    )
    (net (code "45") (name "Net-(U100-GND)") (class "Default")
      (node (ref "R100") (pin "2") (pinfunction "2_2") (pintype "passive"))
      (node (ref "R102") (pin "1") (pinfunction "1_1") (pintype "passive"))
      (node (ref "U100") (pin "2") (pinfunction "GND_2") (pintype "power_in"))
    )
    (net (code "46") (name "Net-(U100-SET)") (class "Default")
      (node (ref "R102") (pin "2") (pinfunction "2_2") (pintype "passive"))
      (node (ref "U100") (pin "3") (pinfunction "SET_3") (pintype "bidirectional"))
    )
    (net (code "47") (name "Net-(U100-V+)") (class "Default")
      (node (ref "R104") (pin "2") (pinfunction "2_2") (pintype "passive"))
      (node (ref "U100") (pin "5") (pinfunction "V+_5") (pintype "power_in"))
    )
    (net (code "48") (name "Net-(U101-DIV)") (class "Default")
      (node (ref "R103") (pin "2") (pinfunction "2_2") (pintype "passive"))
      (node (ref "R105") (pin "1") (pinfunction "1_1") (pintype "passive"))
      (node (ref "U101") (pin "6") (pinfunction "DIV_6") (pintype "bidirectional"))
    )
    (net (code "49") (name "Net-(U101-OUT)") (class "Default")
      (node (ref "R106") (pin "1") (pinfunction "1_1") (pintype "passive"))
      (node (ref "R27") (pin "2") (pinfunction "2_2") (pintype "passive"))
      (node (ref "U101") (pin "4") (pinfunction "OUT_4") (pintype "bidirectional"))
    )
    (net (code "50") (name "Net-(U101-SET)") (class "Default")
      (node (ref "R101") (pin "2") (pinfunction "2_2") (pintype "passive"))
      (node (ref "U101") (pin "3") (pinfunction "SET_3") (pintype "bidirectional"))
    )
    (net (code "51") (name "Net-(U102-ADJ)") (class "Default")
      (node (ref "R112") (pin "2") (pinfunction "2_2") (pintype "passive"))
      (node (ref "R113") (pin "1") (pinfunction "1_1") (pintype "passive"))
      (node (ref "U102") (pin "3") (pinfunction "ADJ_3") (pintype "input"))
    )
    (net (code "52") (name "Net-(U102-IN)") (class "Default")
      (node (ref "C2") (pin "1") (pinfunction "1_1") (pintype "passive"))
      (node (ref "C3") (pin "1") (pinfunction "1_1") (pintype "passive"))
      (node (ref "D102") (pin "C") (pinfunction "C_C") (pintype "passive"))
      (node (ref "R2") (pin "2") (pinfunction "2_2") (pintype "passive"))
      (node (ref "U102") (pin "1") (pinfunction "IN_1") (pintype "power_in"))
    )
    (net (code "53") (name "Net-(U103-+IN)") (class "Default")
      (node (ref "C10") (pin "1") (pinfunction "1_1") (pintype "passive"))
      (node (ref "C6") (pin "1") (pinfunction "1_1") (pintype "passive"))
      (node (ref "C9") (pin "1") (pinfunction "1_1") (pintype "passive"))
      (node (ref "L1") (pin "1") (pinfunction "1_1") (pintype "passive"))
      (node (ref "L2") (pin "1") (pinfunction "1_1") (pintype "passive"))
      (node (ref "U103") (pin "1") (pinfunction "+IN_1") (pintype "power_in"))
    )
    (net (code "54") (name "Net-(U103-FLT)") (class "Default")
      (node (ref "R4") (pin "1") (pinfunction "1_1") (pintype "passive"))
      (node (ref "U103") (pin "4") (pinfunction "FLT_4") (pintype "output"))
    )
    (net (code "55") (name "Net-(U103-TR)") (class "Default")
      (node (ref "R111") (pin "1") (pinfunction "1_1") (pintype "passive"))
      (node (ref "U103") (pin "2") (pinfunction "TR_2") (pintype "output"))
    )
    (net (code "56") (name "PACK+") (class "Default")
      (node (ref "J3") (pin "5") (pinfunction "5_5") (pintype "passive"))
      (node (ref "K1") (pin "1") (pinfunction "CONTACT1_1") (pintype "bidirectional"))
      (node (ref "K3") (pin "4") (pinfunction "CONTACT2_4") (pintype "bidirectional"))
      (node (ref "TP6") (pin "1") (pinfunction "P$1_1") (pintype "passive"))
    )
    (net (code "57") (name "PACK+FUSED") (class "Default")
      (node (ref "R11") (pin "2") (pinfunction "2_2") (pintype "passive"))
      (node (ref "R22") (pin "1") (pinfunction "1_1") (pintype "passive"))
      (node (ref "TP8") (pin "1") (pinfunction "P$1_1") (pintype "passive"))
    )
    (net (code "58") (name "PRECHARGE_OK") (class "Default")
      (node (ref "C106") (pin "1") (pinfunction "1_1") (pintype "passive"))
      (node (ref "J4") (pin "3") (pinfunction "3_3") (pintype "passive"))
      (node (ref "R29") (pin "2") (pinfunction "2_2") (pintype "passive"))
      (node (ref "TP18") (pin "1") (pinfunction "P$1_1") (pintype "passive"))
      (node (ref "U100") (pin "1") (pinfunction "IN_1") (pintype "bidirectional"))
    )
    (net (code "59") (name "P_DO") (class "Default")
      (node (ref "R14") (pin "1") (pinfunction "1_1") (pintype "passive"))
      (node (ref "R16") (pin "2") (pinfunction "2_2") (pintype "passive"))
      (node (ref "R18") (pin "2") (pinfunction "2_2") (pintype "passive"))
      (node (ref "R20") (pin "1") (pinfunction "1_1") (pintype "passive"))
      (node (ref "TP13") (pin "1") (pinfunction "P$1_1") (pintype "passive"))
    )
    (net (code "60") (name "SHDN") (class "Default")
      (node (ref "D100") (pin "C") (pinfunction "C_C") (pintype "passive"))
      (node (ref "D101") (pin "C") (pinfunction "C_C") (pintype "passive"))
      (node (ref "J4") (pin "2") (pinfunction "2_2") (pintype "passive"))
      (node (ref "K1") (pin "2") (pinfunction "COIL+_2") (pintype "bidirectional"))
      (node (ref "K2") (pin "2") (pinfunction "COIL+_2") (pintype "bidirectional"))
      (node (ref "R30") (pin "2") (pinfunction "2_2") (pintype "passive"))
      (node (ref "R31") (pin "2") (pinfunction "2_2") (pintype "passive"))
      (node (ref "TP21") (pin "1") (pinfunction "P$1_1") (pintype "passive"))
    )
    (net (code "61") (name "TS+5V") (class "Default")
      (node (ref "C12") (pin "1") (pinfunction "1_1") (pintype "passive"))
      (node (ref "C13") (pin "1") (pinfunction "1_1") (pintype "passive"))
      (node (ref "C14") (pin "1") (pinfunction "1_1") (pintype "passive"))
      (node (ref "C17") (pin "1") (pinfunction "1_1") (pintype "passive"))
      (node (ref "C18") (pin "1") (pinfunction "1_1") (pintype "passive"))
      (node (ref "C21") (pin "1") (pinfunction "1_1") (pintype "passive"))
      (node (ref "C22") (pin "1") (pinfunction "1_1") (pintype "passive"))
      (node (ref "L3") (pin "2") (pinfunction "2_2") (pintype "passive"))
      (node (ref "R6") (pin "2") (pinfunction "2_2") (pintype "passive"))
      (node (ref "R9") (pin "1") (pinfunction "1_1") (pintype "passive"))
      (node (ref "TP3") (pin "1") (pinfunction "P$1_1") (pintype "passive"))
      (node (ref "U1") (pin "9") (pinfunction "VFB_9") (pintype "input"))
      (node (ref "U2") (pin "3") (pinfunction "VDD1_3") (pintype "power_in"))
      (node (ref "U3") (pin "3") (pinfunction "VDD1_3") (pintype "power_in"))
    )
    (net (code "62") (name "TS+FUSED") (class "Default")
      (node (ref "F1") (pin "2") (pinfunction "2_2") (pintype "passive"))
      (node (ref "J3") (pin "4") (pinfunction "4_4") (pintype "passive"))
      (node (ref "L2") (pin "2") (pinfunction "2_2") (pintype "passive"))
      (node (ref "R12") (pin "2") (pinfunction "2_2") (pintype "passive"))
      (node (ref "R2") (pin "1") (pinfunction "1_1") (pintype "passive"))
      (node (ref "R3") (pin "2") (pinfunction "2_2") (pintype "passive"))
    )
    (net (code "63") (name "TS+UNFUSED") (class "Default")
      (node (ref "F1") (pin "1") (pinfunction "1_1") (pintype "passive"))
      (node (ref "J3") (pin "1") (pinfunction "1_1") (pintype "passive"))
      (node (ref "J3") (pin "2") (pinfunction "2_2") (pintype "passive"))
      (node (ref "K2") (pin "1") (pinfunction "CONTACT1_1") (pintype "bidirectional"))
      (node (ref "R10") (pin "2") (pinfunction "2_2") (pintype "passive"))
      (node (ref "R7") (pin "1") (pinfunction "1_1") (pintype "passive"))
      (node (ref "TP10") (pin "1") (pinfunction "P$1_1") (pintype "passive"))
    )
    (net (code "64") (name "TS-FUSED") (class "Default")
      (node (ref "C10") (pin "2") (pinfunction "2_2") (pintype "passive"))
      (node (ref "C109") (pin "2") (pinfunction "2_2") (pintype "passive"))
      (node (ref "C11") (pin "2") (pinfunction "2_2") (pintype "passive"))
      (node (ref "C12") (pin "2") (pinfunction "2_2") (pintype "passive"))
      (node (ref "C13") (pin "2") (pinfunction "2_2") (pintype "passive"))
      (node (ref "C14") (pin "2") (pinfunction "2_2") (pintype "passive"))
      (node (ref "C15") (pin "2") (pinfunction "2_2") (pintype "passive"))
      (node (ref "C16") (pin "2") (pinfunction "2_2") (pintype "passive"))
      (node (ref "C17") (pin "2") (pinfunction "2_2") (pintype "passive"))
      (node (ref "C18") (pin "2") (pinfunction "2_2") (pintype "passive"))
      (node (ref "C19") (pin "2") (pinfunction "2_2") (pintype "passive"))
      (node (ref "C2") (pin "2") (pinfunction "2_2") (pintype "passive"))
      (node (ref "C20") (pin "2") (pinfunction "2_2") (pintype "passive"))
      (node (ref "C21") (pin "2") (pinfunction "2_2") (pintype "passive"))
      (node (ref "C22") (pin "2") (pinfunction "2_2") (pintype "passive"))
      (node (ref "C3") (pin "2") (pinfunction "2_2") (pintype "passive"))
      (node (ref "C4") (pin "2") (pinfunction "2_2") (pintype "passive"))
      (node (ref "C5") (pin "2") (pinfunction "2_2") (pintype "passive"))
      (node (ref "C6") (pin "2") (pinfunction "2_2") (pintype "passive"))
      (node (ref "C8") (pin "2") (pinfunction "2_2") (pintype "passive"))
      (node (ref "C9") (pin "2") (pinfunction "2_2") (pintype "passive"))
      (node (ref "D2") (pin "1") (pinfunction "C_1") (pintype "passive"))
      (node (ref "D4") (pin "1") (pinfunction "C_1") (pintype "passive"))
      (node (ref "F2") (pin "2") (pinfunction "2_2") (pintype "passive"))
      (node (ref "J2") (pin "1") (pinfunction "1_1") (pintype "passive"))
      (node (ref "J2") (pin "2") (pinfunction "2_2") (pintype "passive"))
      (node (ref "K100") (pin "3") (pinfunction "CONTACT1_3") (pintype "bidirectional"))
      (node (ref "R107") (pin "1") (pinfunction "1_1") (pintype "passive"))
      (node (ref "R108") (pin "1") (pinfunction "1_1") (pintype "passive"))
      (node (ref "R111") (pin "2") (pinfunction "2_2") (pintype "passive"))
      (node (ref "R112") (pin "1") (pinfunction "1_1") (pintype "passive"))
      (node (ref "R16") (pin "1") (pinfunction "1_1") (pintype "passive"))
      (node (ref "R17") (pin "1") (pinfunction "1_1") (pintype "passive"))
      (node (ref "R18") (pin "1") (pinfunction "1_1") (pintype "passive"))
      (node (ref "R19") (pin "1") (pinfunction "1_1") (pintype "passive"))
      (node (ref "TP7") (pin "1") (pinfunction "P$1_1") (pintype "passive"))
      (node (ref "U1") (pin "16") (pinfunction "GND_16") (pintype "power_in"))
      (node (ref "U1") (pin "6") (pinfunction "VPRG2_6") (pintype "input"))
      (node (ref "U1") (pin "8") (pinfunction "GND_8") (pintype "power_in"))
      (node (ref "U103") (pin "5") (pinfunction "-IN_5") (pintype "power_in"))
      (node (ref "U2") (pin "4") (pinfunction "GND1_4") (pintype "power_in"))
      (node (ref "U3") (pin "4") (pinfunction "GND1_4") (pintype "power_in"))
    )
    (net (code "65") (name "TS-UNFUSED") (class "Default")
      (node (ref "F2") (pin "1") (pinfunction "1_1") (pintype "passive"))
      (node (ref "J2") (pin "5") (pinfunction "5_5") (pintype "passive"))
      (node (ref "R13") (pin "1") (pinfunction "1_1") (pintype "passive"))
      (node (ref "R8") (pin "1") (pinfunction "1_1") (pintype "passive"))
      (node (ref "TP11") (pin "1") (pinfunction "P$1_1") (pintype "passive"))
    )
    (net (code "66") (name "TSMP+") (class "Default")
      (node (ref "J3") (pin "3") (pinfunction "3_3") (pintype "passive"))
      (node (ref "R7") (pin "2") (pinfunction "2_2") (pintype "passive"))
      (node (ref "TP4") (pin "1") (pinfunction "P$1_1") (pintype "passive"))
    )
    (net (code "67") (name "TSMP-") (class "Default")
      (node (ref "J2") (pin "4") (pinfunction "4_4") (pintype "passive"))
      (node (ref "R8") (pin "2") (pinfunction "2_2") (pintype "passive"))
      (node (ref "TP5") (pin "1") (pinfunction "P$1_1") (pintype "passive"))
    )
    (net (code "68") (name "TS_DO") (class "Default")
      (node (ref "R15") (pin "1") (pinfunction "1_1") (pintype "passive"))
      (node (ref "R17") (pin "2") (pinfunction "2_2") (pintype "passive"))
      (node (ref "R19") (pin "2") (pinfunction "2_2") (pintype "passive"))
      (node (ref "R21") (pin "1") (pinfunction "1_1") (pintype "passive"))
      (node (ref "TP12") (pin "1") (pinfunction "P$1_1") (pintype "passive"))
    )
    (net (code "69") (name "unconnected-(U1-FBO-Pad5)") (class "Default")
      (node (ref "U1") (pin "5") (pinfunction "FBO_5") (pintype "output"))
    )
  )
)
